# SCH_STM32CRONOS_SQUEM.net
KiCad netlist of a schematic drawn in EasyEDA
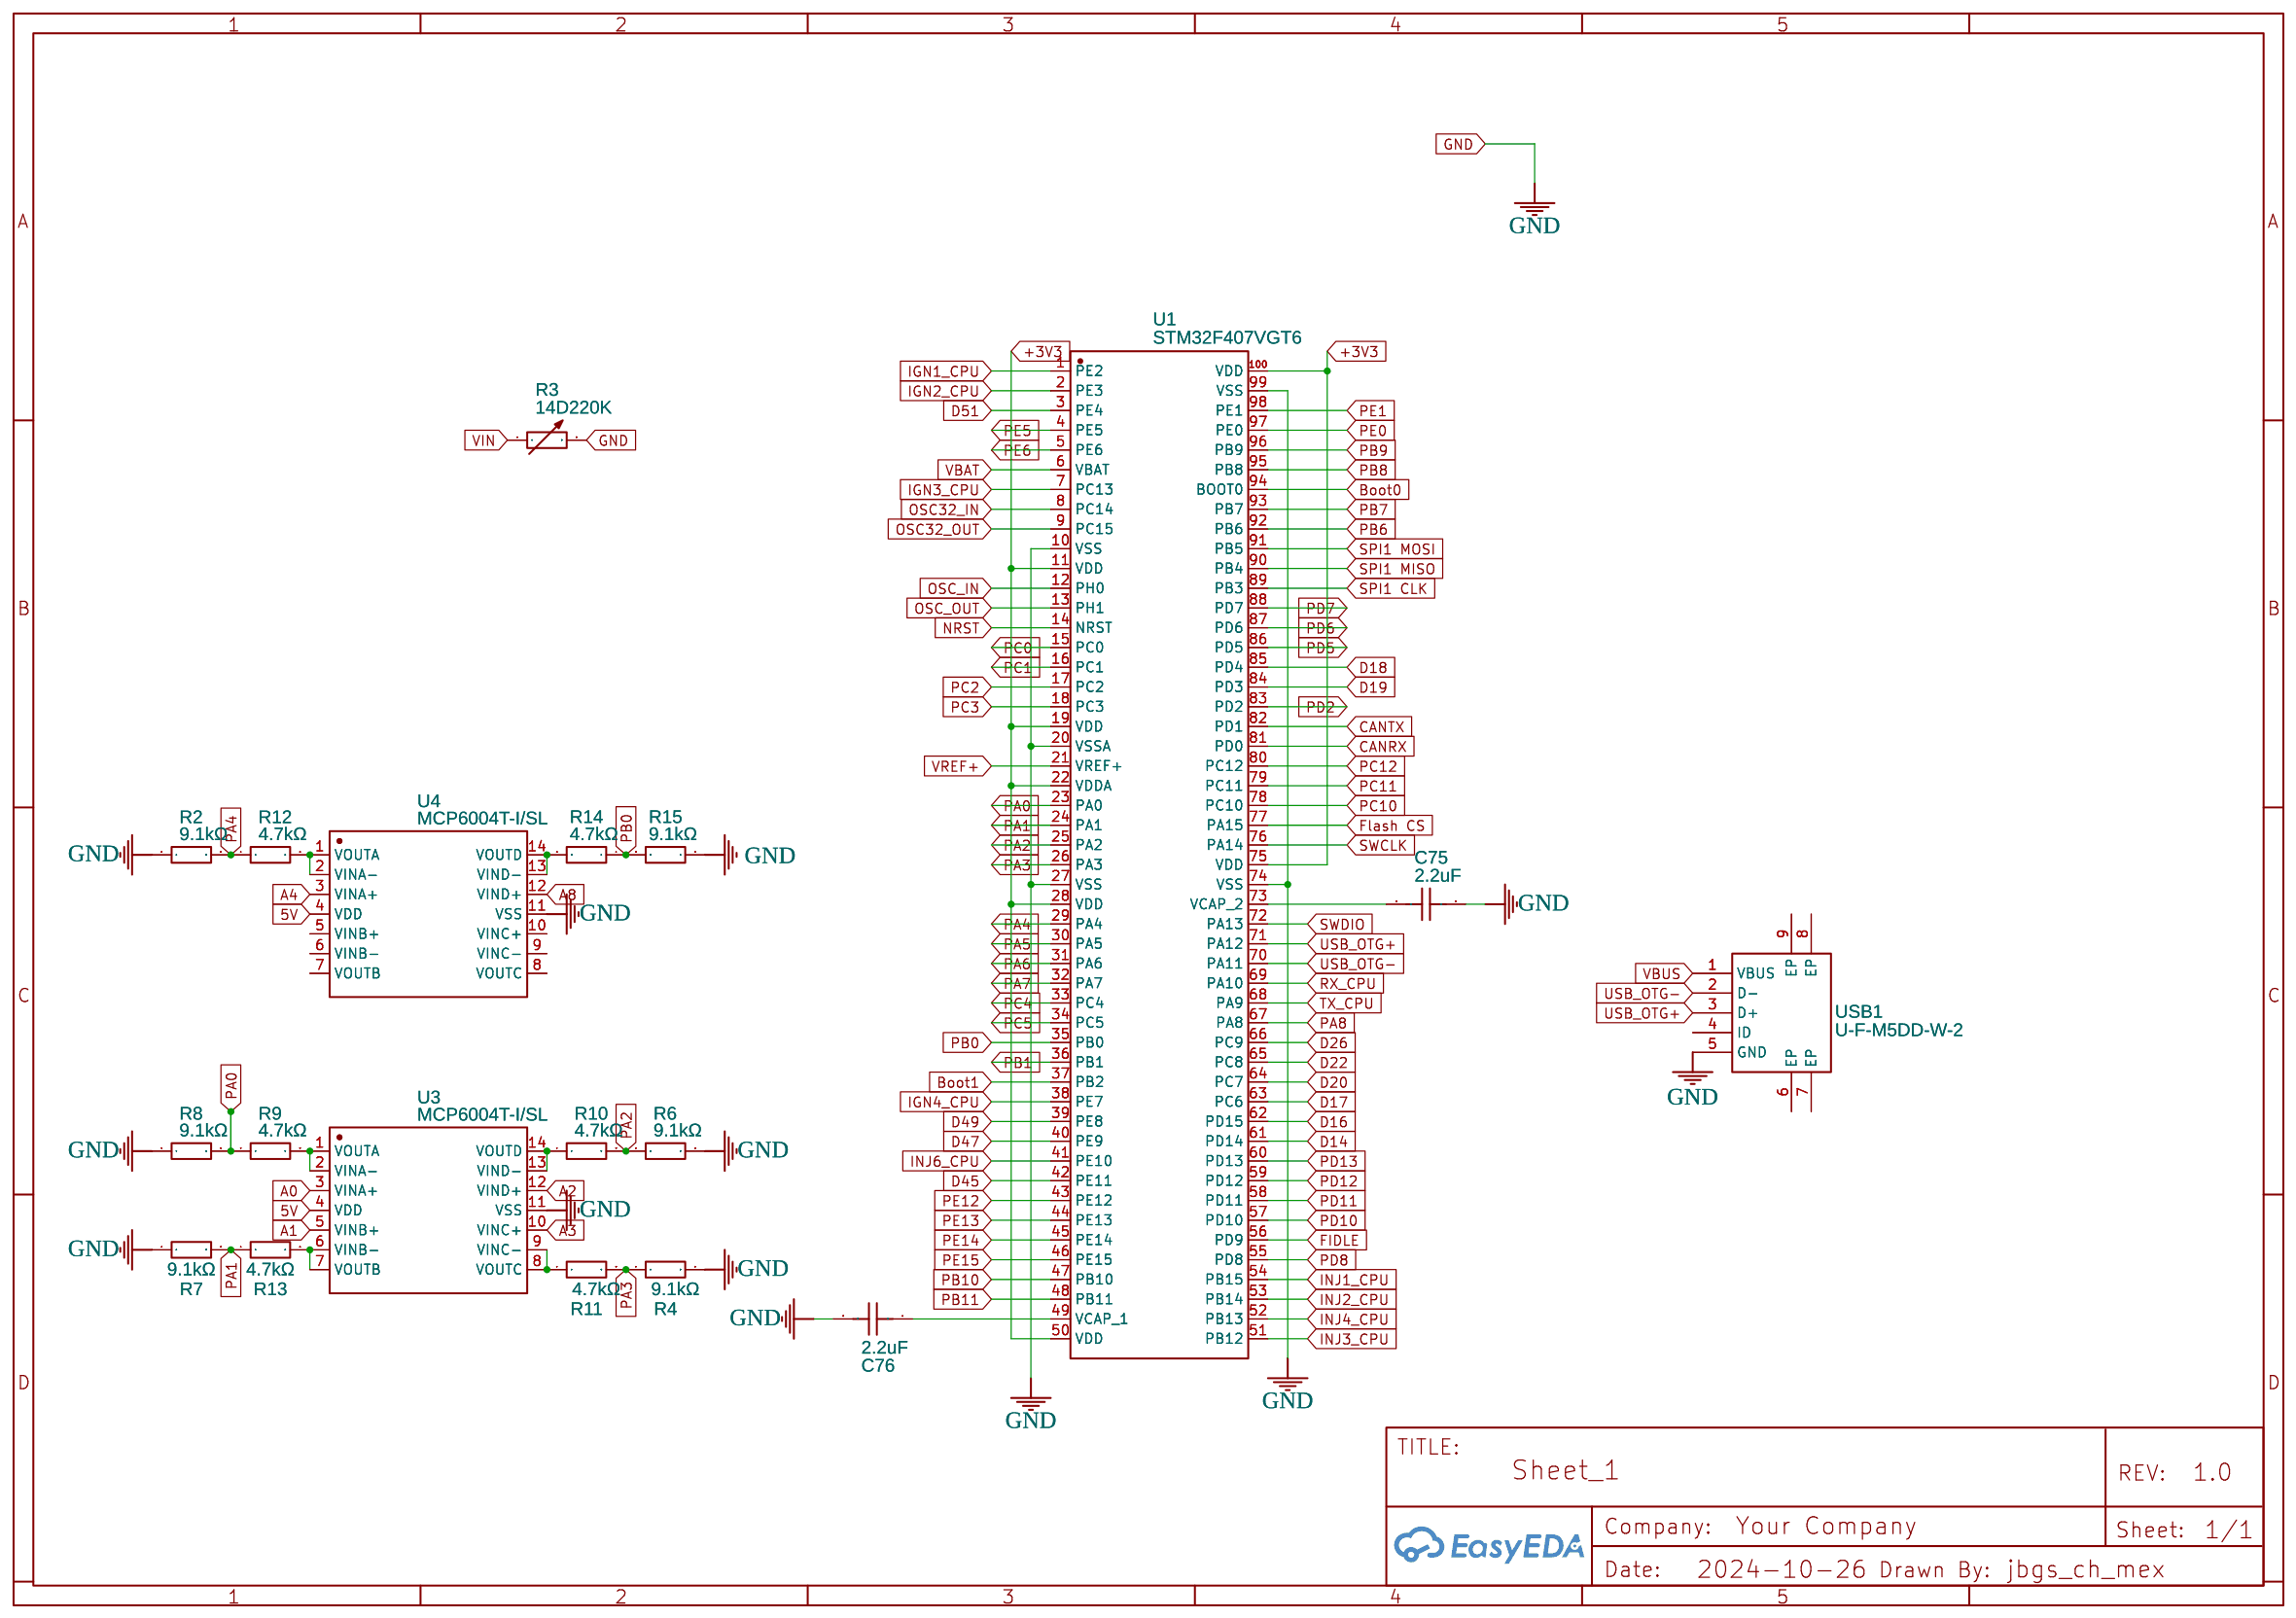
[diagram p0: Sheet_1]
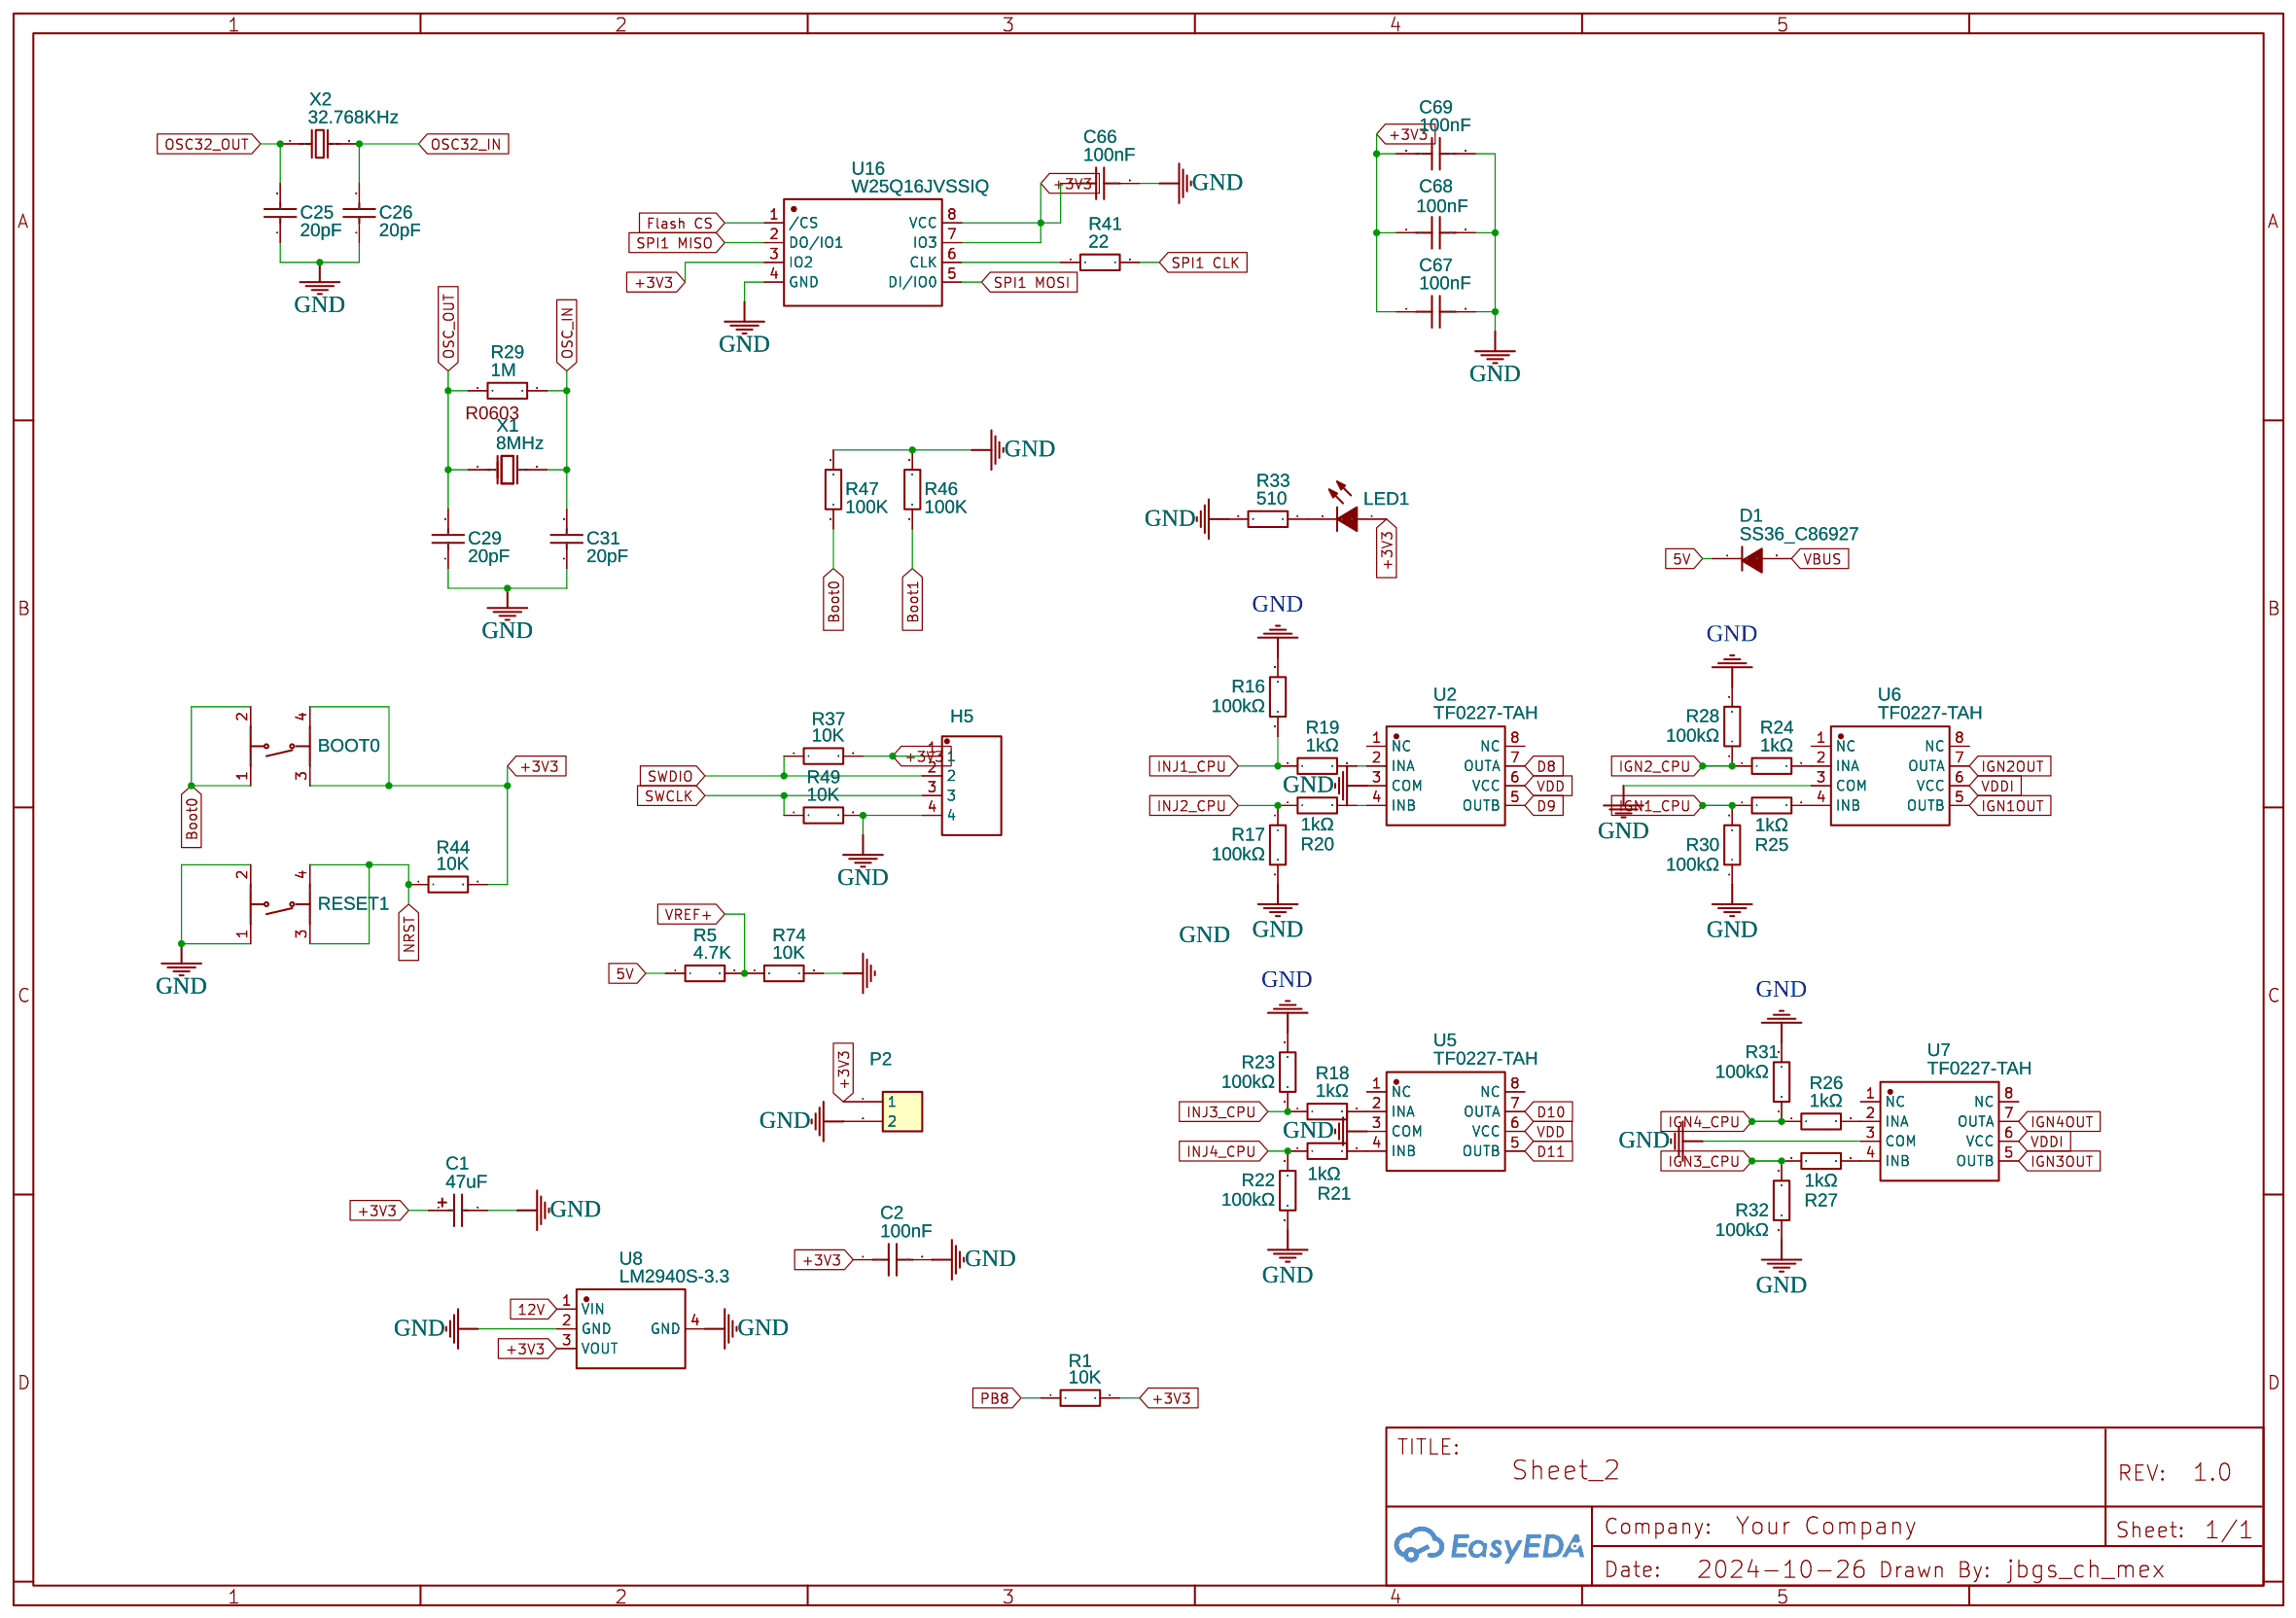
[diagram p1: Sheet_2]
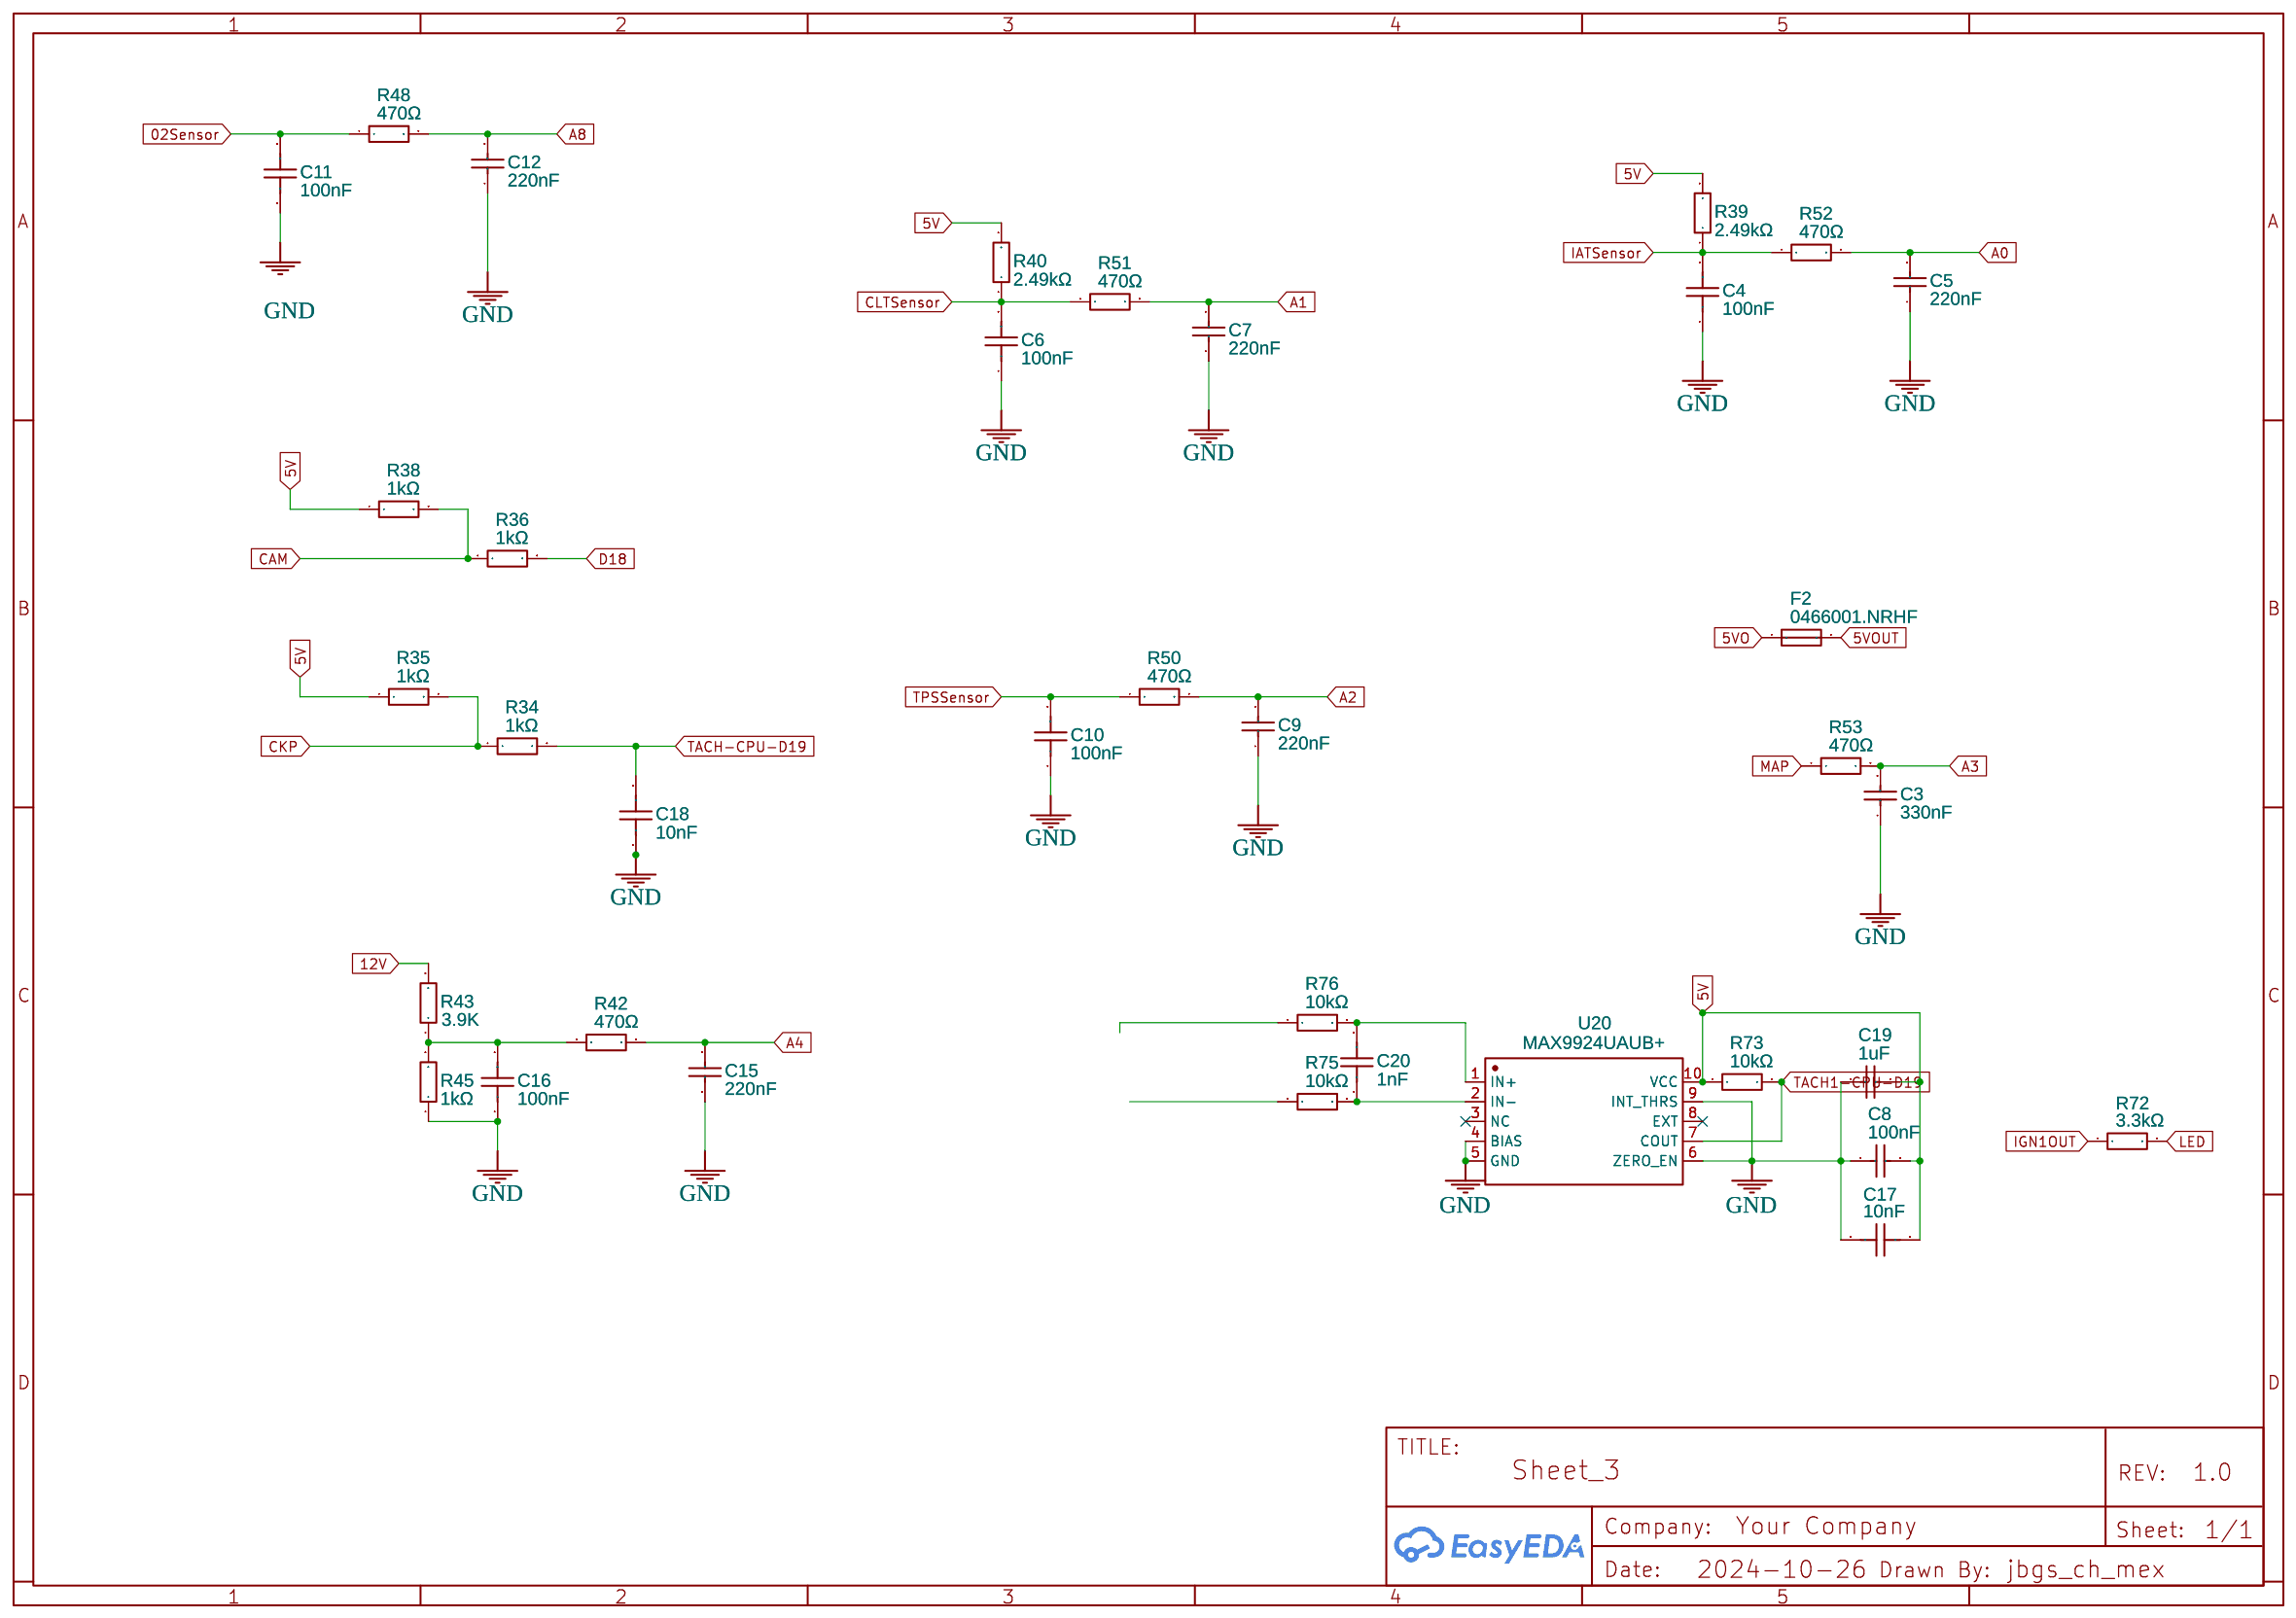
[diagram p2: Sheet_3]
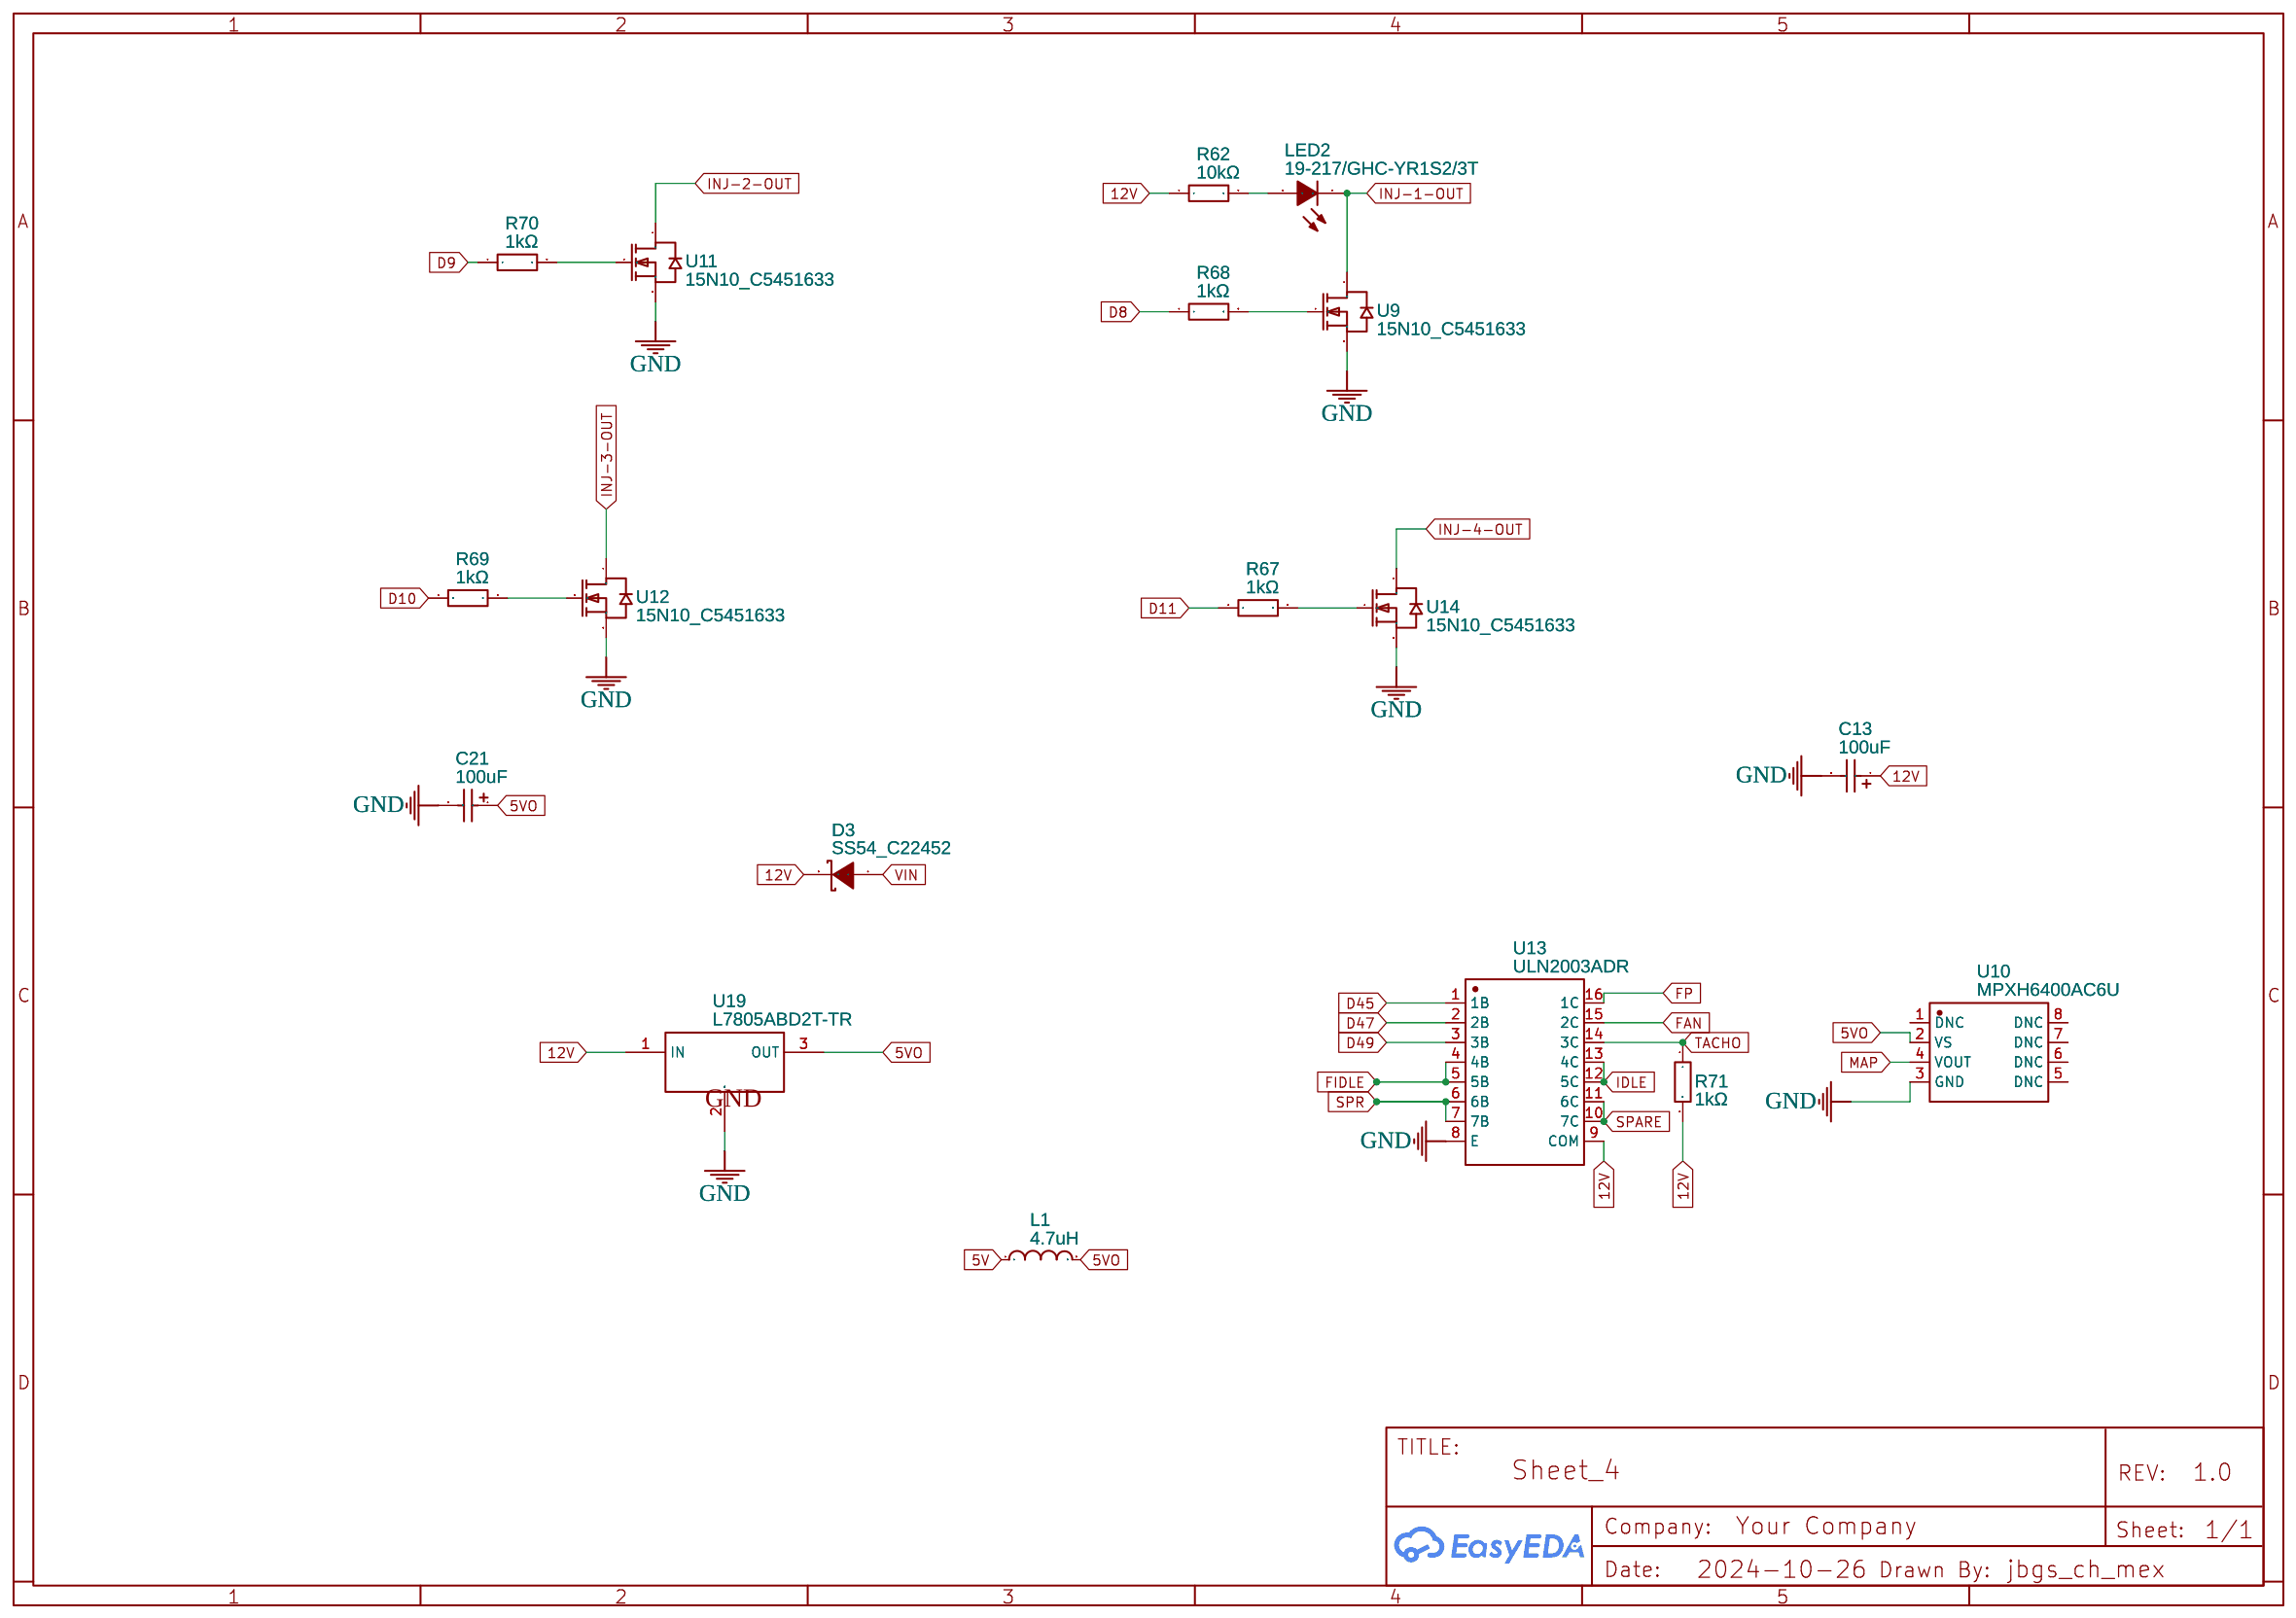
[diagram p3: Sheet_4]

(export (version "E")
  (design (tool "Eeschema 10.0.6"))
  (components
    (comp (ref "C75")
      (value "2.2uF")
      (fields (field (name "Manufacturer Part") "CL10A225KA8NNNC") (field (name "Manufacturer") "SAMSUNG"))
      (libsource (lib "") (part "CL10A225KA8NNNC_1"))
    )
    (comp (ref "C76")
      (value "2.2uF")
      (fields (field (name "Manufacturer Part") "CL10A225KA8NNNC") (field (name "Manufacturer") "SAMSUNG"))
      (libsource (lib "") (part "CL10A225KA8NNNC"))
    )
    (comp (ref "R2")
      (value "9.1kΩ")
      (fields
        (field (name "Manufacturer Part") "0603WAF9101T5E")
        (field (name "Manufacturer") "UNI-ROYAL(厚声)")
      )
      (libsource (lib "") (part "0603WAF9101T5E"))
    )
    (comp (ref "R3")
      (value "14D220K")
      (fields (field (name "Manufacturer") "HEL(鸿志)"))
      (libsource (lib "") (part "14D220K"))
    )
    (comp (ref "R4")
      (value "9.1kΩ")
      (fields
        (field (name "Manufacturer Part") "0603WAF9101T5E")
        (field (name "Manufacturer") "UNI-ROYAL(厚声)")
      )
      (libsource (lib "") (part "0603WAF9101T5E"))
    )
    (comp (ref "R6")
      (value "9.1kΩ")
      (fields
        (field (name "Manufacturer Part") "0603WAF9101T5E")
        (field (name "Manufacturer") "UNI-ROYAL(厚声)")
      )
      (libsource (lib "") (part "0603WAF9101T5E"))
    )
    (comp (ref "R7")
      (value "9.1kΩ")
      (fields
        (field (name "Manufacturer Part") "0603WAF9101T5E")
        (field (name "Manufacturer") "UNI-ROYAL(厚声)")
      )
      (libsource (lib "") (part "0603WAF9101T5E"))
    )
    (comp (ref "R8")
      (value "9.1kΩ")
      (fields
        (field (name "Manufacturer Part") "0603WAF9101T5E")
        (field (name "Manufacturer") "UNI-ROYAL(厚声)")
      )
      (libsource (lib "") (part "0603WAF9101T5E"))
    )
    (comp (ref "R9")
      (value "4.7kΩ")
      (fields (field (name "Manufacturer Part") "RMC06034K7FN") (field (name "Manufacturer") "Tyohm(幸亚电阻)"))
      (libsource (lib "") (part "RMC06034.7K1%N"))
    )
    (comp (ref "R10")
      (value "4.7kΩ")
      (fields (field (name "Manufacturer Part") "RMC06034K7FN") (field (name "Manufacturer") "Tyohm(幸亚电阻)"))
      (libsource (lib "") (part "RMC06034.7K1%N"))
    )
    (comp (ref "R11")
      (value "4.7kΩ")
      (fields (field (name "Manufacturer Part") "RMC06034K7FN") (field (name "Manufacturer") "Tyohm(幸亚电阻)"))
      (libsource (lib "") (part "RMC06034.7K1%N"))
    )
    (comp (ref "R12")
      (value "4.7kΩ")
      (fields (field (name "Manufacturer Part") "RMC06034K7FN") (field (name "Manufacturer") "Tyohm(幸亚电阻)"))
      (libsource (lib "") (part "RMC06034.7K1%N"))
    )
    (comp (ref "R13")
      (value "4.7kΩ")
      (fields (field (name "Manufacturer Part") "RMC06034K7FN") (field (name "Manufacturer") "Tyohm(幸亚电阻)"))
      (libsource (lib "") (part "RMC06034.7K1%N"))
    )
    (comp (ref "R14")
      (value "4.7kΩ")
      (fields (field (name "Manufacturer Part") "RMC06034K7FN") (field (name "Manufacturer") "Tyohm(幸亚电阻)"))
      (libsource (lib "") (part "RMC06034.7K1%N_1"))
    )
    (comp (ref "R15")
      (value "9.1kΩ")
      (fields
        (field (name "Manufacturer Part") "0603WAF9101T5E")
        (field (name "Manufacturer") "UNI-ROYAL(厚声)")
      )
      (libsource (lib "") (part "0603WAF9101T5E_1"))
    )
    (comp (ref "U1")
      (value "STM32F407VGT6")
      (fields (field (name "Manufacturer") "ST(意法半导体)"))
      (libsource (lib "") (part "STM32F407VGT6"))
    )
    (comp (ref "U3")
      (value "MCP6004T-I/SL")
      (fields (field (name "Manufacturer") "MICROCHIP(美国微芯)"))
      (libsource (lib "") (part "MCP6004T-I/SL"))
    )
    (comp (ref "U4")
      (value "MCP6004T-I/SL")
      (fields (field (name "Manufacturer") "MICROCHIP(美国微芯)"))
      (libsource (lib "") (part "MCP6004T-I/SL"))
    )
    (comp (ref "USB1")
      (value "U-F-M5DD-W-2")
      (fields (field (name "Manufacturer") "韩国韩荣"))
      (libsource (lib "") (part "U-F-M5DD-W-2"))
    )
    (comp (ref "BOOT0")
      (value "TS-1089S-02526")
      (fields (field (name "Manufacturer") "XUNPU"))
      (libsource (lib "") (part "TS-1089S-02526_1"))
    )
    (comp (ref "C1")
      (value "47uF")
      (fields (field (name "Manufacturer Part") "TAJA476K006RNJ") (field (name "Manufacturer") "Kyocera AVX"))
      (libsource (lib "") (part "TAJA476K006RNJ"))
    )
    (comp (ref "C2")
      (value "100nF")
      (fields
        (field (name "Manufacturer Part") "CC0603KRX7R9BB104")
        (field (name "Manufacturer") "YAGEO(国巨)")
      )
      (libsource (lib "") (part "CC0603KRX7R9BB104"))
    )
    (comp (ref "C25") (value "20pF") (libsource (lib "") (part "CL05C200JB5NNNC")))
    (comp (ref "C26") (value "20pF") (libsource (lib "") (part "CL05C200JB5NNNC")))
    (comp (ref "C29") (value "20pF") (libsource (lib "") (part "CL05C200JB5NNNC")))
    (comp (ref "C31") (value "20pF") (libsource (lib "") (part "CL05C200JB5NNNC")))
    (comp (ref "C66")
      (value "100nF")
      (fields
        (field (name "Manufacturer Part") "C0603X104K050T")
        (field (name "Manufacturer") "Holy Stone Enterprise")
      )
      (libsource (lib "") (part "C0603X104K050T"))
    )
    (comp (ref "C67")
      (value "100nF")
      (fields
        (field (name "Manufacturer Part") "C0603X104K050T")
        (field (name "Manufacturer") "Holy Stone Enterprise")
      )
      (libsource (lib "") (part "C0603X104K050T"))
    )
    (comp (ref "C68")
      (value "100nF")
      (fields
        (field (name "Manufacturer Part") "C0603X104K050T")
        (field (name "Manufacturer") "Holy Stone Enterprise")
      )
      (libsource (lib "") (part "C0603X104K050T"))
    )
    (comp (ref "C69")
      (value "100nF")
      (fields
        (field (name "Manufacturer Part") "C0603X104K050T")
        (field (name "Manufacturer") "Holy Stone Enterprise")
      )
      (libsource (lib "") (part "C0603X104K050T"))
    )
    (comp (ref "D1")
      (value "SS36_C86927")
      (fields (field (name "Manufacturer Part") "SS36") (field (name "Manufacturer") "DIYI(迪一/芯诺)"))
      (libsource (lib "") (part "SS36_C86927"))
    )
    (comp (ref "H5")
      (value "Header-Male-2.54_1x4_C124378")
      (fields
        (field (name "Manufacturer Part") "210S-1*4P L=11.6MMGold-plated black")
        (field (name "Manufacturer") "Ckmtw")
      )
      (libsource (lib "") (part "Header-Male-2.54_1x4_C124378"))
    )
    (comp (ref "LED1")
      (value "19-217/BHC-ZL1M2RY/3T")
      (fields (field (name "Manufacturer") "EVERLIGHT"))
      (libsource (lib "") (part "19-217/BHC-ZL1M2RY/3T"))
    )
    (comp (ref "P2")
      (value "Female header1*2P copy")
      (fields (field (name "Manufacturer Part") "Female header1*2P") (field (name "Manufacturer") "BOOMELE"))
      (libsource (lib "") (part "Female header1*2P copy"))
    )
    (comp (ref "R1")
      (value "10K")
      (fields (field (name "Manufacturer Part") "RC0402FR-0710KL") (field (name "Manufacturer") "YAGEO"))
      (libsource (lib "") (part "RC0402FR-0710KL"))
    )
    (comp (ref "R5")
      (value "4.7K")
      (fields (field (name "Manufacturer Part") "0603WAF4701T5E") (field (name "Manufacturer") "UniOhm"))
      (libsource (lib "") (part "0603WAF4701T5E"))
    )
    (comp (ref "R16")
      (value "100kΩ")
      (fields
        (field (name "Manufacturer Part") "0603WAF1003T5E")
        (field (name "Manufacturer") "UNI-ROYAL(厚声)")
      )
      (libsource (lib "") (part "0603WAF1003T5E"))
    )
    (comp (ref "R17")
      (value "100kΩ")
      (fields
        (field (name "Manufacturer Part") "0603WAF1003T5E")
        (field (name "Manufacturer") "UNI-ROYAL(厚声)")
      )
      (libsource (lib "") (part "0603WAF1003T5E_1"))
    )
    (comp (ref "R18")
      (value "1kΩ")
      (fields
        (field (name "Manufacturer Part") "0603WAF1001T5E")
        (field (name "Manufacturer") "UNI-ROYAL(厚声)")
      )
      (libsource (lib "") (part "0603WAF1001T5E"))
    )
    (comp (ref "R19")
      (value "1kΩ")
      (fields
        (field (name "Manufacturer Part") "0603WAF1001T5E")
        (field (name "Manufacturer") "UNI-ROYAL(厚声)")
      )
      (libsource (lib "") (part "0603WAF1001T5E"))
    )
    (comp (ref "R20")
      (value "1kΩ")
      (fields
        (field (name "Manufacturer Part") "0603WAF1001T5E")
        (field (name "Manufacturer") "UNI-ROYAL(厚声)")
      )
      (libsource (lib "") (part "0603WAF1001T5E"))
    )
    (comp (ref "R21")
      (value "1kΩ")
      (fields
        (field (name "Manufacturer Part") "0603WAF1001T5E")
        (field (name "Manufacturer") "UNI-ROYAL(厚声)")
      )
      (libsource (lib "") (part "0603WAF1001T5E"))
    )
    (comp (ref "R22")
      (value "100kΩ")
      (fields
        (field (name "Manufacturer Part") "0603WAF1003T5E")
        (field (name "Manufacturer") "UNI-ROYAL(厚声)")
      )
      (libsource (lib "") (part "0603WAF1003T5E_1"))
    )
    (comp (ref "R23")
      (value "100kΩ")
      (fields
        (field (name "Manufacturer Part") "0603WAF1003T5E")
        (field (name "Manufacturer") "UNI-ROYAL(厚声)")
      )
      (libsource (lib "") (part "0603WAF1003T5E"))
    )
    (comp (ref "R24")
      (value "1kΩ")
      (fields
        (field (name "Manufacturer Part") "0603WAF1001T5E")
        (field (name "Manufacturer") "UNI-ROYAL(厚声)")
      )
      (libsource (lib "") (part "0603WAF1001T5E"))
    )
    (comp (ref "R25")
      (value "1kΩ")
      (fields
        (field (name "Manufacturer Part") "0603WAF1001T5E")
        (field (name "Manufacturer") "UNI-ROYAL(厚声)")
      )
      (libsource (lib "") (part "0603WAF1001T5E"))
    )
    (comp (ref "R26")
      (value "1kΩ")
      (fields
        (field (name "Manufacturer Part") "0603WAF1001T5E")
        (field (name "Manufacturer") "UNI-ROYAL(厚声)")
      )
      (libsource (lib "") (part "0603WAF1001T5E"))
    )
    (comp (ref "R27")
      (value "1kΩ")
      (fields
        (field (name "Manufacturer Part") "0603WAF1001T5E")
        (field (name "Manufacturer") "UNI-ROYAL(厚声)")
      )
      (libsource (lib "") (part "0603WAF1001T5E"))
    )
    (comp (ref "R28")
      (value "100kΩ")
      (fields
        (field (name "Manufacturer Part") "0603WAF1003T5E")
        (field (name "Manufacturer") "UNI-ROYAL(厚声)")
      )
      (libsource (lib "") (part "0603WAF1003T5E"))
    )
    (comp (ref "R29")
      (value "1M")
      (fields (field (name "Manufacturer Part") "0402WGF1004TCE") (field (name "Manufacturer") "UniOhm"))
      (libsource (lib "") (part "0402WGF1004TCE"))
    )
    (comp (ref "R30")
      (value "100kΩ")
      (fields
        (field (name "Manufacturer Part") "0603WAF1003T5E")
        (field (name "Manufacturer") "UNI-ROYAL(厚声)")
      )
      (libsource (lib "") (part "0603WAF1003T5E"))
    )
    (comp (ref "R31")
      (value "100kΩ")
      (fields
        (field (name "Manufacturer Part") "0603WAF1003T5E")
        (field (name "Manufacturer") "UNI-ROYAL(厚声)")
      )
      (libsource (lib "") (part "0603WAF1003T5E"))
    )
    (comp (ref "R32")
      (value "100kΩ")
      (fields
        (field (name "Manufacturer Part") "0603WAF1003T5E")
        (field (name "Manufacturer") "UNI-ROYAL(厚声)")
      )
      (libsource (lib "") (part "0603WAF1003T5E"))
    )
    (comp (ref "R33")
      (value "510")
      (fields (field (name "Manufacturer Part") "0603WAF5100T5E") (field (name "Manufacturer") "UniOhm"))
      (libsource (lib "") (part "0603WAF5100T5E"))
    )
    (comp (ref "R37")
      (value "10K")
      (fields (field (name "Manufacturer Part") "RC0402FR-0710KL") (field (name "Manufacturer") "YAGEO"))
      (libsource (lib "") (part "RC0402FR-0710KL"))
    )
    (comp (ref "R41")
      (value "22")
      (fields (field (name "Manufacturer Part") "RC0402JR-0722RL") (field (name "Manufacturer") "YAGEO"))
      (libsource (lib "") (part "RC0402JR-0722RL"))
    )
    (comp (ref "R44") (value "10K") (libsource (lib "") (part "RC0402FR-0710KL")))
    (comp (ref "R46")
      (value "100K")
      (fields (field (name "Manufacturer Part") "RC0603JR-07100KL") (field (name "Manufacturer") "YAGEO"))
      (libsource (lib "") (part "RC0603JR-07100KL"))
    )
    (comp (ref "R47")
      (value "100K")
      (fields (field (name "Manufacturer Part") "RC0603JR-07100KL") (field (name "Manufacturer") "YAGEO"))
      (libsource (lib "") (part "RC0603JR-07100KL"))
    )
    (comp (ref "R49")
      (value "10K")
      (fields (field (name "Manufacturer Part") "RC0402FR-0710KL") (field (name "Manufacturer") "YAGEO"))
      (libsource (lib "") (part "RC0402FR-0710KL"))
    )
    (comp (ref "R74")
      (value "10K")
      (fields (field (name "Manufacturer Part") "0603WAF1002T5E") (field (name "Manufacturer") "UniOhm"))
      (libsource (lib "") (part "0603WAF1002T5E"))
    )
    (comp (ref "RESET1")
      (value "TS-1089S-02526")
      (fields (field (name "Manufacturer") "XUNPU"))
      (libsource (lib "") (part "TS-1089S-02526"))
    )
    (comp (ref "U2")
      (value "TF0227-TAH")
      (fields (field (name "Manufacturer") "TFSS(德律风根)"))
      (libsource (lib "") (part "TF0227-TAH"))
    )
    (comp (ref "U5")
      (value "TF0227-TAH")
      (fields (field (name "Manufacturer") "TFSS(德律风根)"))
      (libsource (lib "") (part "TF0227-TAH"))
    )
    (comp (ref "U6")
      (value "TF0227-TAH")
      (fields (field (name "Manufacturer") "TFSS(德律风根)"))
      (libsource (lib "") (part "TF0227-TAH"))
    )
    (comp (ref "U7")
      (value "TF0227-TAH")
      (fields (field (name "Manufacturer") "TFSS(德律风根)"))
      (libsource (lib "") (part "TF0227-TAH"))
    )
    (comp (ref "U8")
      (value "LM2940S-3.3")
      (fields (field (name "Manufacturer") "HTC"))
      (libsource (lib "") (part "LM2940S-3.3"))
    )
    (comp (ref "U16") (value "W25Q16JVSSIQ") (libsource (lib "") (part "W25Q16JVSSIQ")))
    (comp (ref "X1")
      (value "8MHz")
      (fields (field (name "Manufacturer Part") "X50328MSB2GI") (field (name "Manufacturer") "YXC"))
      (libsource (lib "") (part "X50328MSB2GI"))
    )
    (comp (ref "X2")
      (value "32.768KHz")
      (fields (field (name "Manufacturer Part") "Q13FC1350000400") (field (name "Manufacturer") "EPSON"))
      (libsource (lib "") (part "Q13FC1350000400"))
    )
    (comp (ref "C3")
      (value "330nF")
      (fields (field (name "Manufacturer Part") "0603B334K250NT") (field (name "Manufacturer") "FH(风华)"))
      (libsource (lib "") (part "0603B334K250NT"))
    )
    (comp (ref "C4")
      (value "100nF")
      (fields
        (field (name "Manufacturer Part") "CC0603KRX7R9BB104")
        (field (name "Manufacturer") "YAGEO(国巨)")
      )
      (libsource (lib "") (part "CC0603KRX7R9BB104"))
    )
    (comp (ref "C5")
      (value "220nF")
      (fields
        (field (name "Manufacturer Part") "CL10B224KA8NNNC")
        (field (name "Manufacturer") "SAMSUNG(三星)")
      )
      (libsource (lib "") (part "CL10B224KA8NNNC"))
    )
    (comp (ref "C6")
      (value "100nF")
      (fields
        (field (name "Manufacturer Part") "CC0603KRX7R9BB104")
        (field (name "Manufacturer") "YAGEO(国巨)")
      )
      (libsource (lib "") (part "CC0603KRX7R9BB104"))
    )
    (comp (ref "C7")
      (value "220nF")
      (fields
        (field (name "Manufacturer Part") "CL10B224KA8NNNC")
        (field (name "Manufacturer") "SAMSUNG(三星)")
      )
      (libsource (lib "") (part "CL10B224KA8NNNC"))
    )
    (comp (ref "C8")
      (value "100nF")
      (fields
        (field (name "Manufacturer Part") "CL21B104KCFNNNE")
        (field (name "Manufacturer") "SAMSUNG(三星)")
      )
      (libsource (lib "") (part "CL21B104KCFNNNE"))
    )
    (comp (ref "C9")
      (value "220nF")
      (fields
        (field (name "Manufacturer Part") "CL10B224KA8NNNC")
        (field (name "Manufacturer") "SAMSUNG(三星)")
      )
      (libsource (lib "") (part "CL10B224KA8NNNC"))
    )
    (comp (ref "C10")
      (value "100nF")
      (fields
        (field (name "Manufacturer Part") "CC0603KRX7R9BB104")
        (field (name "Manufacturer") "YAGEO(国巨)")
      )
      (libsource (lib "") (part "CC0603KRX7R9BB104"))
    )
    (comp (ref "C11")
      (value "100nF")
      (fields
        (field (name "Manufacturer Part") "CC0603KRX7R9BB104")
        (field (name "Manufacturer") "YAGEO(国巨)")
      )
      (libsource (lib "") (part "CC0603KRX7R9BB104"))
    )
    (comp (ref "C12")
      (value "220nF")
      (fields
        (field (name "Manufacturer Part") "CL10B224KA8NNNC")
        (field (name "Manufacturer") "SAMSUNG(三星)")
      )
      (libsource (lib "") (part "CL10B224KA8NNNC"))
    )
    (comp (ref "C15")
      (value "220nF")
      (fields
        (field (name "Manufacturer Part") "CL10B224KA8NNNC")
        (field (name "Manufacturer") "SAMSUNG(三星)")
      )
      (libsource (lib "") (part "CL10B224KA8NNNC"))
    )
    (comp (ref "C16")
      (value "100nF")
      (fields
        (field (name "Manufacturer Part") "CC0603KRX7R9BB104")
        (field (name "Manufacturer") "YAGEO(国巨)")
      )
      (libsource (lib "") (part "CC0603KRX7R9BB104"))
    )
    (comp (ref "C17")
      (value "10nF")
      (fields
        (field (name "Manufacturer Part") "TCC0805X7R103K500DT")
        (field (name "Manufacturer") "CCTC(三环)")
      )
      (libsource (lib "") (part "TCC0805X7R103K500DT"))
    )
    (comp (ref "C18")
      (value "10nF")
      (fields (field (name "Manufacturer Part") "C0805C103K1RAC7800") (field (name "Manufacturer") "KEMET"))
      (libsource (lib "") (part "C0805C103K1RAC7800"))
    )
    (comp (ref "C19")
      (value "1uF")
      (fields
        (field (name "Manufacturer Part") "CC0805KKX7R9BB105")
        (field (name "Manufacturer") "YAGEO(国巨)")
      )
      (libsource (lib "") (part "CC0805KKX7R9BB105"))
    )
    (comp (ref "C20")
      (value "1nF")
      (fields
        (field (name "Manufacturer Part") "CC0805KRX7RZBB102")
        (field (name "Manufacturer") "YAGEO(国巨)")
      )
      (libsource (lib "") (part "CC0805KRX7RZBB102"))
    )
    (comp (ref "F2")
      (value "0466001.NRHF")
      (fields (field (name "Manufacturer") "Littelfuse(美国力特)"))
      (libsource (lib "") (part "0466001.NRHF"))
    )
    (comp (ref "R34")
      (value "1kΩ")
      (fields
        (field (name "Manufacturer Part") "0805W8F1001T5E")
        (field (name "Manufacturer") "UNI-ROYAL(厚声)")
      )
      (libsource (lib "") (part "0805W8F1001T5E"))
    )
    (comp (ref "R35")
      (value "1kΩ")
      (fields
        (field (name "Manufacturer Part") "0805W8F1001T5E")
        (field (name "Manufacturer") "UNI-ROYAL(厚声)")
      )
      (libsource (lib "") (part "0805W8F1001T5E"))
    )
    (comp (ref "R36")
      (value "1kΩ")
      (fields
        (field (name "Manufacturer Part") "0603WAF1001T5E")
        (field (name "Manufacturer") "UNI-ROYAL(厚声)")
      )
      (libsource (lib "") (part "0603WAF1001T5E"))
    )
    (comp (ref "R38")
      (value "1kΩ")
      (fields
        (field (name "Manufacturer Part") "0603WAF1001T5E")
        (field (name "Manufacturer") "UNI-ROYAL(厚声)")
      )
      (libsource (lib "") (part "0603WAF1001T5E"))
    )
    (comp (ref "R39")
      (value "2.49kΩ")
      (fields
        (field (name "Manufacturer Part") "0805W8F2491T5E")
        (field (name "Manufacturer") "UNI-ROYAL(厚声)")
      )
      (libsource (lib "") (part "0805W8F2491T5E"))
    )
    (comp (ref "R40")
      (value "2.49kΩ")
      (fields
        (field (name "Manufacturer Part") "0805W8F2491T5E")
        (field (name "Manufacturer") "UNI-ROYAL(厚声)")
      )
      (libsource (lib "") (part "0805W8F2491T5E"))
    )
    (comp (ref "R42")
      (value "470Ω")
      (fields
        (field (name "Manufacturer Part") "0603WAF4700T5E")
        (field (name "Manufacturer") "UNI-ROYAL(厚声)")
      )
      (libsource (lib "") (part "0603WAF4700T5E"))
    )
    (comp (ref "R43")
      (value "3.9K")
      (fields (field (name "Manufacturer Part") "0603WAF3901T5E") (field (name "Manufacturer") "UniOhm"))
      (libsource (lib "") (part "0603WAF3901T5E"))
    )
    (comp (ref "R45")
      (value "1kΩ")
      (fields
        (field (name "Manufacturer Part") "0603WAF1001T5E")
        (field (name "Manufacturer") "UNI-ROYAL(厚声)")
      )
      (libsource (lib "") (part "0603WAF1001T5E_1"))
    )
    (comp (ref "R48")
      (value "470Ω")
      (fields
        (field (name "Manufacturer Part") "0603WAF4700T5E")
        (field (name "Manufacturer") "UNI-ROYAL(厚声)")
      )
      (libsource (lib "") (part "0603WAF4700T5E"))
    )
    (comp (ref "R50")
      (value "470Ω")
      (fields
        (field (name "Manufacturer Part") "0603WAF4700T5E")
        (field (name "Manufacturer") "UNI-ROYAL(厚声)")
      )
      (libsource (lib "") (part "0603WAF4700T5E"))
    )
    (comp (ref "R51")
      (value "470Ω")
      (fields
        (field (name "Manufacturer Part") "0603WAF4700T5E")
        (field (name "Manufacturer") "UNI-ROYAL(厚声)")
      )
      (libsource (lib "") (part "0603WAF4700T5E"))
    )
    (comp (ref "R52")
      (value "470Ω")
      (fields
        (field (name "Manufacturer Part") "0603WAF4700T5E")
        (field (name "Manufacturer") "UNI-ROYAL(厚声)")
      )
      (libsource (lib "") (part "0603WAF4700T5E"))
    )
    (comp (ref "R53")
      (value "470Ω")
      (fields
        (field (name "Manufacturer Part") "0603WAF4700T5E")
        (field (name "Manufacturer") "UNI-ROYAL(厚声)")
      )
      (libsource (lib "") (part "0603WAF4700T5E"))
    )
    (comp (ref "R72")
      (value "3.3kΩ")
      (fields
        (field (name "Manufacturer Part") "0805W8F3301T5E")
        (field (name "Manufacturer") "UNI-ROYAL(厚声)")
      )
      (libsource (lib "") (part "0805W8F3301T5E"))
    )
    (comp (ref "R73")
      (value "10kΩ")
      (fields
        (field (name "Manufacturer Part") "0805W8F1002T5E")
        (field (name "Manufacturer") "UNI-ROYAL(厚声)")
      )
      (libsource (lib "") (part "0805W8F1002T5E"))
    )
    (comp (ref "R75")
      (value "10kΩ")
      (fields
        (field (name "Manufacturer Part") "0805W8F1002T5E")
        (field (name "Manufacturer") "UNI-ROYAL(厚声)")
      )
      (libsource (lib "") (part "0805W8F1002T5E"))
    )
    (comp (ref "R76")
      (value "10kΩ")
      (fields
        (field (name "Manufacturer Part") "0805W8F1002T5E")
        (field (name "Manufacturer") "UNI-ROYAL(厚声)")
      )
      (libsource (lib "") (part "0805W8F1002T5E"))
    )
    (comp (ref "U20")
      (value "MAX9924UAUB+")
      (fields (field (name "Manufacturer") "ADI(亚德诺)/MAXIM(美信)"))
      (libsource (lib "") (part "MAX9924UAUB+"))
    )
    (comp (ref "C13")
      (value "100uF")
      (fields (field (name "Manufacturer Part") "TAJD107M020RNJ") (field (name "Manufacturer") "Kyocera AVX"))
      (libsource (lib "") (part "TAJD107M020RNJ"))
    )
    (comp (ref "C21")
      (value "100uF")
      (fields (field (name "Manufacturer Part") "TAJB107K006RNJ") (field (name "Manufacturer") "Kyocera AVX"))
      (libsource (lib "") (part "TAJB107K006RNJ"))
    )
    (comp (ref "D3")
      (value "SS54_C22452")
      (fields (field (name "Manufacturer Part") "SS54") (field (name "Manufacturer") "MDD(辰达半导体)"))
      (libsource (lib "") (part "SS54_C22452"))
    )
    (comp (ref "L1")
      (value "4.7uH")
      (fields (field (name "Manufacturer Part") "YSPI0530-4R7M") (field (name "Manufacturer") "YJYCOIN(益嘉源)"))
      (libsource (lib "") (part "YSPI0530-4R7M"))
    )
    (comp (ref "LED2")
      (value "19-217/GHC-YR1S2/3T")
      (fields (field (name "Manufacturer") "EVERLIGHT(亿光)"))
      (libsource (lib "") (part "19-217/GHC-YR1S2/3T"))
    )
    (comp (ref "R62")
      (value "10kΩ")
      (fields
        (field (name "Manufacturer Part") "0805W8F1002T5E")
        (field (name "Manufacturer") "UNI-ROYAL(厚声)")
      )
      (libsource (lib "") (part "0805W8F1002T5E"))
    )
    (comp (ref "R67")
      (value "1kΩ")
      (fields
        (field (name "Manufacturer Part") "0805W8F1001T5E")
        (field (name "Manufacturer") "UNI-ROYAL(厚声)")
      )
      (libsource (lib "") (part "0805W8F1001T5E"))
    )
    (comp (ref "R68")
      (value "1kΩ")
      (fields
        (field (name "Manufacturer Part") "0805W8F1001T5E")
        (field (name "Manufacturer") "UNI-ROYAL(厚声)")
      )
      (libsource (lib "") (part "0805W8F1001T5E"))
    )
    (comp (ref "R69")
      (value "1kΩ")
      (fields
        (field (name "Manufacturer Part") "0805W8F1001T5E")
        (field (name "Manufacturer") "UNI-ROYAL(厚声)")
      )
      (libsource (lib "") (part "0805W8F1001T5E"))
    )
    (comp (ref "R70")
      (value "1kΩ")
      (fields
        (field (name "Manufacturer Part") "0805W8F1001T5E")
        (field (name "Manufacturer") "UNI-ROYAL(厚声)")
      )
      (libsource (lib "") (part "0805W8F1001T5E"))
    )
    (comp (ref "R71")
      (value "1kΩ")
      (fields
        (field (name "Manufacturer Part") "0603WAF1001T5E")
        (field (name "Manufacturer") "UNI-ROYAL(厚声)")
      )
      (libsource (lib "") (part "0603WAF1001T5E"))
    )
    (comp (ref "U9")
      (value "15N10_C5451633")
      (fields (field (name "Manufacturer Part") "15N10") (field (name "Manufacturer") "HXY MOSFET(华轩阳电子)"))
      (libsource (lib "") (part "15N10_C5451633"))
    )
    (comp (ref "U10")
      (value "MPXH6400AC6U")
      (fields (field (name "Manufacturer") "NXP(恩智浦)"))
      (libsource (lib "") (part "MPXH6400AC6U"))
    )
    (comp (ref "U11")
      (value "15N10_C5451633")
      (fields (field (name "Manufacturer Part") "15N10") (field (name "Manufacturer") "HXY MOSFET(华轩阳电子)"))
      (libsource (lib "") (part "15N10_C5451633"))
    )
    (comp (ref "U12")
      (value "15N10_C5451633")
      (fields (field (name "Manufacturer Part") "15N10") (field (name "Manufacturer") "HXY MOSFET(华轩阳电子)"))
      (libsource (lib "") (part "15N10_C5451633"))
    )
    (comp (ref "U13")
      (value "ULN2003ADR")
      (fields (field (name "Manufacturer") "TI(德州仪器)"))
      (libsource (lib "") (part "ULN2003ADR"))
    )
    (comp (ref "U14")
      (value "15N10_C5451633")
      (fields (field (name "Manufacturer Part") "15N10") (field (name "Manufacturer") "HXY MOSFET(华轩阳电子)"))
      (libsource (lib "") (part "15N10_C5451633"))
    )
    (comp (ref "U19")
      (value "L7805ABD2T-TR")
      (fields (field (name "Manufacturer") "ST(意法半导体)"))
      (libsource (lib "") (part "L7805ABD2T-TR"))
    )
  )
  (nets
    (net (code "1") (name "+3V3") (class "Default")
      (node (ref "BOOT0") (pin "3") (pinfunction "3_3") (pintype "unspecified"))
      (node (ref "BOOT0") (pin "4") (pinfunction "4_4") (pintype "unspecified"))
      (node (ref "C1") (pin "1") (pinfunction "1_1") (pintype "input"))
      (node (ref "C2") (pin "1") (pinfunction "1_1") (pintype "unspecified"))
      (node (ref "C66") (pin "1") (pinfunction "1_1") (pintype "unspecified"))
      (node (ref "C67") (pin "1") (pinfunction "1_1") (pintype "unspecified"))
      (node (ref "C68") (pin "1") (pinfunction "1_1") (pintype "unspecified"))
      (node (ref "C69") (pin "1") (pinfunction "1_1") (pintype "unspecified"))
      (node (ref "H5") (pin "1") (pinfunction "1_1") (pintype "unspecified"))
      (node (ref "LED1") (pin "1") (pinfunction "A_1") (pintype "input"))
      (node (ref "P2") (pin "1") (pinfunction "1_1") (pintype "input"))
      (node (ref "R1") (pin "2") (pinfunction "2_2") (pintype "input"))
      (node (ref "R37") (pin "2") (pinfunction "2_2") (pintype "input"))
      (node (ref "R44") (pin "2") (pinfunction "2_2") (pintype "input"))
      (node (ref "U1") (pin "100") (pinfunction "VDD_100") (pintype "unspecified"))
      (node (ref "U1") (pin "11") (pinfunction "VDD_11") (pintype "unspecified"))
      (node (ref "U1") (pin "19") (pinfunction "VDD_19") (pintype "unspecified"))
      (node (ref "U1") (pin "22") (pinfunction "VDDA_22") (pintype "unspecified"))
      (node (ref "U1") (pin "28") (pinfunction "VDD_28") (pintype "unspecified"))
      (node (ref "U1") (pin "50") (pinfunction "VDD_50") (pintype "unspecified"))
      (node (ref "U1") (pin "75") (pinfunction "VDD_75") (pintype "unspecified"))
      (node (ref "U16") (pin "3") (pinfunction "IO2_3") (pintype "unspecified"))
      (node (ref "U16") (pin "7") (pinfunction "IO3_7") (pintype "unspecified"))
      (node (ref "U16") (pin "8") (pinfunction "VCC_8") (pintype "unspecified"))
      (node (ref "U8") (pin "3") (pinfunction "VOUT_3") (pintype "unspecified"))
    )
    (net (code "2") (name "02Sensor") (class "Default")
      (node (ref "C11") (pin "2") (pinfunction "2_2") (pintype "unspecified"))
      (node (ref "R48") (pin "1") (pinfunction "1_1") (pintype "input"))
    )
    (net (code "3") (name "5V") (class "Default")
      (node (ref "C17") (pin "1") (pinfunction "1_1") (pintype "unspecified"))
      (node (ref "C19") (pin "2") (pinfunction "2_2") (pintype "input"))
      (node (ref "C8") (pin "2") (pinfunction "2_2") (pintype "input"))
      (node (ref "D1") (pin "1") (pinfunction "C_1") (pintype "unspecified"))
      (node (ref "L1") (pin "1") (pinfunction "1_1") (pintype "unspecified"))
      (node (ref "R35") (pin "1") (pinfunction "1_1") (pintype "input"))
      (node (ref "R38") (pin "1") (pinfunction "1_1") (pintype "input"))
      (node (ref "R39") (pin "2") (pinfunction "2_2") (pintype "input"))
      (node (ref "R40") (pin "2") (pinfunction "2_2") (pintype "input"))
      (node (ref "R5") (pin "1") (pinfunction "1_1") (pintype "input"))
      (node (ref "R73") (pin "1") (pinfunction "1_1") (pintype "input"))
      (node (ref "U20") (pin "10") (pinfunction "VCC_10") (pintype "unspecified"))
      (node (ref "U3") (pin "4") (pinfunction "VDD_4") (pintype "unspecified"))
      (node (ref "U4") (pin "4") (pinfunction "VDD_4") (pintype "unspecified"))
    )
    (net (code "4") (name "5VO") (class "Default")
      (node (ref "C21") (pin "1") (pinfunction "1_1") (pintype "input"))
      (node (ref "F2") (pin "1") (pinfunction "1_1") (pintype "unspecified"))
      (node (ref "L1") (pin "2") (pinfunction "2_2") (pintype "unspecified"))
      (node (ref "U10") (pin "2") (pinfunction "VS_2") (pintype "unspecified"))
      (node (ref "U19") (pin "3") (pinfunction "OUT_3") (pintype "passive"))
    )
    (net (code "5") (name "5VOUT") (class "Default")
      (node (ref "F2") (pin "2") (pinfunction "2_2") (pintype "unspecified"))
    )
    (net (code "6") (name "12V") (class "Default")
      (node (ref "C13") (pin "1") (pinfunction "1_1") (pintype "input"))
      (node (ref "D3") (pin "2") (pinfunction "K_2") (pintype "unspecified"))
      (node (ref "R43") (pin "2") (pinfunction "2_2") (pintype "input"))
      (node (ref "R62") (pin "1") (pinfunction "1_1") (pintype "input"))
      (node (ref "R71") (pin "2") (pinfunction "2_2") (pintype "input"))
      (node (ref "U13") (pin "9") (pinfunction "COM_9") (pintype "unspecified"))
      (node (ref "U19") (pin "1") (pinfunction "IN_1") (pintype "passive"))
      (node (ref "U8") (pin "1") (pinfunction "VIN_1") (pintype "unspecified"))
    )
    (net (code "7") (name "A0") (class "Default")
      (node (ref "C5") (pin "2") (pinfunction "2_2") (pintype "input"))
      (node (ref "R52") (pin "2") (pinfunction "2_2") (pintype "input"))
      (node (ref "U3") (pin "3") (pinfunction "VINA+_3") (pintype "unspecified"))
    )
    (net (code "8") (name "A1") (class "Default")
      (node (ref "C7") (pin "2") (pinfunction "2_2") (pintype "input"))
      (node (ref "R51") (pin "2") (pinfunction "2_2") (pintype "input"))
      (node (ref "U3") (pin "5") (pinfunction "VINB+_5") (pintype "unspecified"))
    )
    (net (code "9") (name "A2") (class "Default")
      (node (ref "C9") (pin "2") (pinfunction "2_2") (pintype "input"))
      (node (ref "R50") (pin "2") (pinfunction "2_2") (pintype "input"))
      (node (ref "U3") (pin "12") (pinfunction "VIND+_12") (pintype "unspecified"))
    )
    (net (code "10") (name "A3") (class "Default")
      (node (ref "C3") (pin "2") (pinfunction "2_2") (pintype "input"))
      (node (ref "R53") (pin "2") (pinfunction "2_2") (pintype "input"))
      (node (ref "U3") (pin "10") (pinfunction "VINC+_10") (pintype "unspecified"))
    )
    (net (code "11") (name "A4") (class "Default")
      (node (ref "C15") (pin "2") (pinfunction "2_2") (pintype "input"))
      (node (ref "R42") (pin "2") (pinfunction "2_2") (pintype "input"))
      (node (ref "U4") (pin "3") (pinfunction "VINA+_3") (pintype "unspecified"))
    )
    (net (code "12") (name "A8") (class "Default")
      (node (ref "C12") (pin "2") (pinfunction "2_2") (pintype "input"))
      (node (ref "R48") (pin "2") (pinfunction "2_2") (pintype "input"))
      (node (ref "U4") (pin "12") (pinfunction "VIND+_12") (pintype "unspecified"))
    )
    (net (code "13") (name "Boot0") (class "Default")
      (node (ref "BOOT0") (pin "1") (pinfunction "1_1") (pintype "unspecified"))
      (node (ref "BOOT0") (pin "2") (pinfunction "2_2") (pintype "unspecified"))
      (node (ref "R47") (pin "1") (pinfunction "1_1") (pintype "unspecified"))
      (node (ref "U1") (pin "94") (pinfunction "BOOT0_94") (pintype "unspecified"))
    )
    (net (code "14") (name "Boot1") (class "Default")
      (node (ref "R46") (pin "1") (pinfunction "1_1") (pintype "unspecified"))
      (node (ref "U1") (pin "37") (pinfunction "PB2_37") (pintype "unspecified"))
    )
    (net (code "15") (name "CAM") (class "Default")
      (node (ref "R36") (pin "1") (pinfunction "1_1") (pintype "input"))
      (node (ref "R38") (pin "2") (pinfunction "2_2") (pintype "input"))
    )
    (net (code "16") (name "CANRX") (class "Default")
      (node (ref "U1") (pin "81") (pinfunction "PD0_81") (pintype "unspecified"))
    )
    (net (code "17") (name "CANTX") (class "Default")
      (node (ref "U1") (pin "82") (pinfunction "PD1_82") (pintype "unspecified"))
    )
    (net (code "18") (name "CKP") (class "Default")
      (node (ref "R34") (pin "1") (pinfunction "1_1") (pintype "input"))
      (node (ref "R35") (pin "2") (pinfunction "2_2") (pintype "input"))
    )
    (net (code "19") (name "CLTSensor") (class "Default")
      (node (ref "C6") (pin "2") (pinfunction "2_2") (pintype "unspecified"))
      (node (ref "R40") (pin "1") (pinfunction "1_1") (pintype "input"))
      (node (ref "R51") (pin "1") (pinfunction "1_1") (pintype "input"))
    )
    (net (code "20") (name "D8") (class "Default")
      (node (ref "R68") (pin "1") (pinfunction "1_1") (pintype "input"))
      (node (ref "U2") (pin "7") (pinfunction "OUTA_7") (pintype "unspecified"))
    )
    (net (code "21") (name "D9") (class "Default")
      (node (ref "R70") (pin "1") (pinfunction "1_1") (pintype "input"))
      (node (ref "U2") (pin "5") (pinfunction "OUTB_5") (pintype "unspecified"))
    )
    (net (code "22") (name "D10") (class "Default")
      (node (ref "R69") (pin "1") (pinfunction "1_1") (pintype "input"))
      (node (ref "U5") (pin "7") (pinfunction "OUTA_7") (pintype "unspecified"))
    )
    (net (code "23") (name "D11") (class "Default")
      (node (ref "R67") (pin "1") (pinfunction "1_1") (pintype "input"))
      (node (ref "U5") (pin "5") (pinfunction "OUTB_5") (pintype "unspecified"))
    )
    (net (code "24") (name "D14") (class "Default")
      (node (ref "U1") (pin "61") (pinfunction "PD14_61") (pintype "unspecified"))
    )
    (net (code "25") (name "D16") (class "Default")
      (node (ref "U1") (pin "62") (pinfunction "PD15_62") (pintype "unspecified"))
    )
    (net (code "26") (name "D17") (class "Default")
      (node (ref "U1") (pin "63") (pinfunction "PC6_63") (pintype "unspecified"))
    )
    (net (code "27") (name "D18") (class "Default")
      (node (ref "R36") (pin "2") (pinfunction "2_2") (pintype "input"))
      (node (ref "U1") (pin "85") (pinfunction "PD4_85") (pintype "unspecified"))
    )
    (net (code "28") (name "D19") (class "Default")
      (node (ref "U1") (pin "84") (pinfunction "PD3_84") (pintype "unspecified"))
    )
    (net (code "29") (name "D20") (class "Default")
      (node (ref "U1") (pin "64") (pinfunction "PC7_64") (pintype "unspecified"))
    )
    (net (code "30") (name "D22") (class "Default")
      (node (ref "U1") (pin "65") (pinfunction "PC8_65") (pintype "unspecified"))
    )
    (net (code "31") (name "D26") (class "Default")
      (node (ref "U1") (pin "66") (pinfunction "PC9_66") (pintype "unspecified"))
    )
    (net (code "32") (name "D45") (class "Default")
      (node (ref "U1") (pin "42") (pinfunction "PE11_42") (pintype "unspecified"))
      (node (ref "U13") (pin "1") (pinfunction "1B_1") (pintype "unspecified"))
    )
    (net (code "33") (name "D47") (class "Default")
      (node (ref "U1") (pin "40") (pinfunction "PE9_40") (pintype "unspecified"))
      (node (ref "U13") (pin "2") (pinfunction "2B_2") (pintype "unspecified"))
    )
    (net (code "34") (name "D49") (class "Default")
      (node (ref "U1") (pin "39") (pinfunction "PE8_39") (pintype "unspecified"))
      (node (ref "U13") (pin "3") (pinfunction "3B_3") (pintype "unspecified"))
    )
    (net (code "35") (name "D51") (class "Default")
      (node (ref "U1") (pin "3") (pinfunction "PE4_3") (pintype "unspecified"))
    )
    (net (code "36") (name "FAN") (class "Default")
      (node (ref "U13") (pin "15") (pinfunction "2C_15") (pintype "unspecified"))
    )
    (net (code "37") (name "FIDLE") (class "Default")
      (node (ref "U1") (pin "56") (pinfunction "PD9_56") (pintype "unspecified"))
      (node (ref "U13") (pin "4") (pinfunction "4B_4") (pintype "unspecified"))
      (node (ref "U13") (pin "5") (pinfunction "5B_5") (pintype "unspecified"))
    )
    (net (code "38") (name "FP") (class "Default")
      (node (ref "U13") (pin "16") (pinfunction "1C_16") (pintype "unspecified"))
    )
    (net (code "39") (name "Flash CS") (class "Default")
      (node (ref "U1") (pin "77") (pinfunction "PA15_77") (pintype "unspecified"))
      (node (ref "U16") (pin "1") (pinfunction "/CS_1") (pintype "unspecified"))
    )
    (net (code "40") (name "GND") (class "Default")
      (node (ref "C1") (pin "2") (pinfunction "2_2") (pintype "input"))
      (node (ref "C10") (pin "1") (pinfunction "1_1") (pintype "unspecified"))
      (node (ref "C11") (pin "1") (pinfunction "1_1") (pintype "unspecified"))
      (node (ref "C12") (pin "1") (pinfunction "1_1") (pintype "input"))
      (node (ref "C13") (pin "2") (pinfunction "2_2") (pintype "input"))
      (node (ref "C15") (pin "1") (pinfunction "1_1") (pintype "input"))
      (node (ref "C16") (pin "1") (pinfunction "1_1") (pintype "unspecified"))
      (node (ref "C17") (pin "2") (pinfunction "2_2") (pintype "unspecified"))
      (node (ref "C18") (pin "1") (pinfunction "1_1") (pintype "unspecified"))
      (node (ref "C19") (pin "1") (pinfunction "1_1") (pintype "input"))
      (node (ref "C2") (pin "2") (pinfunction "2_2") (pintype "unspecified"))
      (node (ref "C21") (pin "2") (pinfunction "2_2") (pintype "input"))
      (node (ref "C25") (pin "1") (pinfunction "1_1") (pintype "input"))
      (node (ref "C26") (pin "1") (pinfunction "1_1") (pintype "input"))
      (node (ref "C29") (pin "1") (pinfunction "1_1") (pintype "input"))
      (node (ref "C3") (pin "1") (pinfunction "1_1") (pintype "input"))
      (node (ref "C31") (pin "1") (pinfunction "1_1") (pintype "input"))
      (node (ref "C4") (pin "1") (pinfunction "1_1") (pintype "unspecified"))
      (node (ref "C5") (pin "1") (pinfunction "1_1") (pintype "input"))
      (node (ref "C6") (pin "1") (pinfunction "1_1") (pintype "unspecified"))
      (node (ref "C66") (pin "2") (pinfunction "2_2") (pintype "unspecified"))
      (node (ref "C67") (pin "2") (pinfunction "2_2") (pintype "unspecified"))
      (node (ref "C68") (pin "2") (pinfunction "2_2") (pintype "unspecified"))
      (node (ref "C69") (pin "2") (pinfunction "2_2") (pintype "unspecified"))
      (node (ref "C7") (pin "1") (pinfunction "1_1") (pintype "input"))
      (node (ref "C75") (pin "1") (pinfunction "1_1") (pintype "unspecified"))
      (node (ref "C76") (pin "2") (pinfunction "2_2") (pintype "unspecified"))
      (node (ref "C8") (pin "1") (pinfunction "1_1") (pintype "input"))
      (node (ref "C9") (pin "1") (pinfunction "1_1") (pintype "input"))
      (node (ref "H5") (pin "4") (pinfunction "4_4") (pintype "unspecified"))
      (node (ref "P2") (pin "2") (pinfunction "2_2") (pintype "input"))
      (node (ref "R15") (pin "1") (pinfunction "1_1") (pintype "input"))
      (node (ref "R16") (pin "2") (pinfunction "2_2") (pintype "input"))
      (node (ref "R17") (pin "2") (pinfunction "2_2") (pintype "input"))
      (node (ref "R2") (pin "1") (pinfunction "1_1") (pintype "input"))
      (node (ref "R22") (pin "2") (pinfunction "2_2") (pintype "input"))
      (node (ref "R23") (pin "2") (pinfunction "2_2") (pintype "input"))
      (node (ref "R28") (pin "2") (pinfunction "2_2") (pintype "input"))
      (node (ref "R3") (pin "2") (pinfunction "2_2") (pintype "unspecified"))
      (node (ref "R30") (pin "1") (pinfunction "1_1") (pintype "input"))
      (node (ref "R31") (pin "2") (pinfunction "2_2") (pintype "input"))
      (node (ref "R32") (pin "1") (pinfunction "1_1") (pintype "input"))
      (node (ref "R33") (pin "2") (pinfunction "2_2") (pintype "input"))
      (node (ref "R4") (pin "2") (pinfunction "2_2") (pintype "input"))
      (node (ref "R45") (pin "1") (pinfunction "1_1") (pintype "input"))
      (node (ref "R46") (pin "2") (pinfunction "2_2") (pintype "unspecified"))
      (node (ref "R47") (pin "2") (pinfunction "2_2") (pintype "unspecified"))
      (node (ref "R49") (pin "2") (pinfunction "2_2") (pintype "input"))
      (node (ref "R6") (pin "2") (pinfunction "2_2") (pintype "input"))
      (node (ref "R7") (pin "1") (pinfunction "1_1") (pintype "input"))
      (node (ref "R74") (pin "2") (pinfunction "2_2") (pintype "input"))
      (node (ref "R8") (pin "1") (pinfunction "1_1") (pintype "input"))
      (node (ref "RESET1") (pin "1") (pinfunction "1_1") (pintype "unspecified"))
      (node (ref "RESET1") (pin "2") (pinfunction "2_2") (pintype "unspecified"))
      (node (ref "U1") (pin "10") (pinfunction "VSS_10") (pintype "unspecified"))
      (node (ref "U1") (pin "20") (pinfunction "VSSA_20") (pintype "unspecified"))
      (node (ref "U1") (pin "27") (pinfunction "VSS_27") (pintype "unspecified"))
      (node (ref "U1") (pin "74") (pinfunction "VSS_74") (pintype "unspecified"))
      (node (ref "U1") (pin "99") (pinfunction "VSS_99") (pintype "unspecified"))
      (node (ref "U10") (pin "3") (pinfunction "GND_3") (pintype "unspecified"))
      (node (ref "U11") (pin "3") (pinfunction "S_3") (pintype "unspecified"))
      (node (ref "U12") (pin "3") (pinfunction "S_3") (pintype "unspecified"))
      (node (ref "U13") (pin "8") (pinfunction "E_8") (pintype "unspecified"))
      (node (ref "U14") (pin "3") (pinfunction "S_3") (pintype "unspecified"))
      (node (ref "U16") (pin "4") (pinfunction "GND_4") (pintype "unspecified"))
      (node (ref "U19") (pin "2") (pinfunction "GND_2") (pintype "passive"))
      (node (ref "U2") (pin "3") (pinfunction "COM_3") (pintype "unspecified"))
      (node (ref "U20") (pin "4") (pinfunction "BIAS_4") (pintype "unspecified"))
      (node (ref "U20") (pin "5") (pinfunction "GND_5") (pintype "unspecified"))
      (node (ref "U20") (pin "6") (pinfunction "ZERO_EN_6") (pintype "unspecified"))
      (node (ref "U20") (pin "9") (pinfunction "INT_THRS_9") (pintype "unspecified"))
      (node (ref "U3") (pin "11") (pinfunction "VSS_11") (pintype "unspecified"))
      (node (ref "U4") (pin "11") (pinfunction "VSS_11") (pintype "unspecified"))
      (node (ref "U5") (pin "3") (pinfunction "COM_3") (pintype "unspecified"))
      (node (ref "U6") (pin "3") (pinfunction "COM_3") (pintype "unspecified"))
      (node (ref "U7") (pin "3") (pinfunction "COM_3") (pintype "unspecified"))
      (node (ref "U8") (pin "2") (pinfunction "GND_2") (pintype "unspecified"))
      (node (ref "U8") (pin "4") (pinfunction "GND_4") (pintype "unspecified"))
      (node (ref "U9") (pin "3") (pinfunction "S_3") (pintype "unspecified"))
      (node (ref "USB1") (pin "5") (pinfunction "GND_5") (pintype "unspecified"))
    )
    (net (code "41") (name "IATSensor") (class "Default")
      (node (ref "C4") (pin "2") (pinfunction "2_2") (pintype "unspecified"))
      (node (ref "R39") (pin "1") (pinfunction "1_1") (pintype "input"))
      (node (ref "R52") (pin "1") (pinfunction "1_1") (pintype "input"))
    )
    (net (code "42") (name "IDLE") (class "Default")
      (node (ref "U13") (pin "12") (pinfunction "5C_12") (pintype "unspecified"))
      (node (ref "U13") (pin "13") (pinfunction "4C_13") (pintype "unspecified"))
    )
    (net (code "43") (name "IGN1OUT") (class "Default")
      (node (ref "R72") (pin "1") (pinfunction "1_1") (pintype "input"))
      (node (ref "U6") (pin "5") (pinfunction "OUTB_5") (pintype "unspecified"))
    )
    (net (code "44") (name "IGN1_CPU") (class "Default")
      (node (ref "R25") (pin "1") (pinfunction "1_1") (pintype "input"))
      (node (ref "R30") (pin "2") (pinfunction "2_2") (pintype "input"))
      (node (ref "U1") (pin "1") (pinfunction "PE2_1") (pintype "unspecified"))
    )
    (net (code "45") (name "IGN2OUT") (class "Default")
      (node (ref "U6") (pin "7") (pinfunction "OUTA_7") (pintype "unspecified"))
    )
    (net (code "46") (name "IGN2_CPU") (class "Default")
      (node (ref "R24") (pin "1") (pinfunction "1_1") (pintype "input"))
      (node (ref "R28") (pin "1") (pinfunction "1_1") (pintype "input"))
      (node (ref "U1") (pin "2") (pinfunction "PE3_2") (pintype "unspecified"))
    )
    (net (code "47") (name "IGN3OUT") (class "Default")
      (node (ref "U7") (pin "5") (pinfunction "OUTB_5") (pintype "unspecified"))
    )
    (net (code "48") (name "IGN3_CPU") (class "Default")
      (node (ref "R27") (pin "1") (pinfunction "1_1") (pintype "input"))
      (node (ref "R32") (pin "2") (pinfunction "2_2") (pintype "input"))
      (node (ref "U1") (pin "7") (pinfunction "PC13_7") (pintype "unspecified"))
    )
    (net (code "49") (name "IGN4OUT") (class "Default")
      (node (ref "U7") (pin "7") (pinfunction "OUTA_7") (pintype "unspecified"))
    )
    (net (code "50") (name "IGN4_CPU") (class "Default")
      (node (ref "R26") (pin "1") (pinfunction "1_1") (pintype "input"))
      (node (ref "R31") (pin "1") (pinfunction "1_1") (pintype "input"))
      (node (ref "U1") (pin "38") (pinfunction "PE7_38") (pintype "unspecified"))
    )
    (net (code "51") (name "INJ-1-OUT") (class "Default")
      (node (ref "LED2") (pin "1") (pinfunction "C_1") (pintype "input"))
      (node (ref "U9") (pin "4") (pinfunction "D_4") (pintype "unspecified"))
    )
    (net (code "52") (name "INJ-2-OUT") (class "Default")
      (node (ref "U11") (pin "4") (pinfunction "D_4") (pintype "unspecified"))
    )
    (net (code "53") (name "INJ-3-OUT") (class "Default")
      (node (ref "U12") (pin "4") (pinfunction "D_4") (pintype "unspecified"))
    )
    (net (code "54") (name "INJ-4-OUT") (class "Default")
      (node (ref "U14") (pin "4") (pinfunction "D_4") (pintype "unspecified"))
    )
    (net (code "55") (name "INJ1_CPU") (class "Default")
      (node (ref "R16") (pin "1") (pinfunction "1_1") (pintype "input"))
      (node (ref "R19") (pin "1") (pinfunction "1_1") (pintype "input"))
      (node (ref "U1") (pin "54") (pinfunction "PB15_54") (pintype "unspecified"))
    )
    (net (code "56") (name "INJ2_CPU") (class "Default")
      (node (ref "R17") (pin "1") (pinfunction "1_1") (pintype "input"))
      (node (ref "R20") (pin "1") (pinfunction "1_1") (pintype "input"))
      (node (ref "U1") (pin "53") (pinfunction "PB14_53") (pintype "unspecified"))
    )
    (net (code "57") (name "INJ3_CPU") (class "Default")
      (node (ref "R18") (pin "1") (pinfunction "1_1") (pintype "input"))
      (node (ref "R23") (pin "1") (pinfunction "1_1") (pintype "input"))
      (node (ref "U1") (pin "51") (pinfunction "PB12_51") (pintype "unspecified"))
    )
    (net (code "58") (name "INJ4_CPU") (class "Default")
      (node (ref "R21") (pin "1") (pinfunction "1_1") (pintype "input"))
      (node (ref "R22") (pin "1") (pinfunction "1_1") (pintype "input"))
      (node (ref "U1") (pin "52") (pinfunction "PB13_52") (pintype "unspecified"))
    )
    (net (code "59") (name "INJ6_CPU") (class "Default")
      (node (ref "U1") (pin "41") (pinfunction "PE10_41") (pintype "unspecified"))
    )
    (net (code "60") (name "LED") (class "Default")
      (node (ref "R72") (pin "2") (pinfunction "2_2") (pintype "input"))
    )
    (net (code "61") (name "MAP") (class "Default")
      (node (ref "R53") (pin "1") (pinfunction "1_1") (pintype "input"))
      (node (ref "U10") (pin "4") (pinfunction "VOUT_4") (pintype "unspecified"))
    )
    (net (code "62") (name "NRST") (class "Default")
      (node (ref "R44") (pin "1") (pinfunction "1_1") (pintype "input"))
      (node (ref "RESET1") (pin "3") (pinfunction "3_3") (pintype "unspecified"))
      (node (ref "RESET1") (pin "4") (pinfunction "4_4") (pintype "unspecified"))
      (node (ref "U1") (pin "14") (pinfunction "NRST_14") (pintype "unspecified"))
    )
    (net (code "63") (name "Net-(C16-Pad2)") (class "Default")
      (node (ref "C16") (pin "2") (pinfunction "2_2") (pintype "unspecified"))
      (node (ref "R42") (pin "1") (pinfunction "1_1") (pintype "input"))
      (node (ref "R43") (pin "1") (pinfunction "1_1") (pintype "input"))
      (node (ref "R45") (pin "2") (pinfunction "2_2") (pintype "input"))
    )
    (net (code "64") (name "Net-(LED1-C)") (class "Default")
      (node (ref "LED1") (pin "2") (pinfunction "C_2") (pintype "input"))
      (node (ref "R33") (pin "1") (pinfunction "1_1") (pintype "input"))
    )
    (net (code "65") (name "Net-(LED2-A)") (class "Default")
      (node (ref "LED2") (pin "2") (pinfunction "A_2") (pintype "input"))
      (node (ref "R62") (pin "2") (pinfunction "2_2") (pintype "input"))
    )
    (net (code "66") (name "Net-(U1-VCAP_1)") (class "Default")
      (node (ref "C76") (pin "1") (pinfunction "1_1") (pintype "unspecified"))
      (node (ref "U1") (pin "49") (pinfunction "VCAP_1_49") (pintype "unspecified"))
    )
    (net (code "67") (name "Net-(U1-VCAP_2)") (class "Default")
      (node (ref "C75") (pin "2") (pinfunction "2_2") (pintype "unspecified"))
      (node (ref "U1") (pin "73") (pinfunction "VCAP_2_73") (pintype "unspecified"))
    )
    (net (code "68") (name "Net-(U2-INA)") (class "Default")
      (node (ref "R19") (pin "2") (pinfunction "2_2") (pintype "input"))
      (node (ref "U2") (pin "2") (pinfunction "INA_2") (pintype "unspecified"))
    )
    (net (code "69") (name "Net-(U2-INB)") (class "Default")
      (node (ref "R20") (pin "2") (pinfunction "2_2") (pintype "input"))
      (node (ref "U2") (pin "4") (pinfunction "INB_4") (pintype "unspecified"))
    )
    (net (code "70") (name "Net-(U3-VINA-)") (class "Default")
      (node (ref "R9") (pin "2") (pinfunction "2_2") (pintype "unspecified"))
      (node (ref "U3") (pin "1") (pinfunction "VOUTA_1") (pintype "unspecified"))
      (node (ref "U3") (pin "2") (pinfunction "VINA-_2") (pintype "unspecified"))
    )
    (net (code "71") (name "Net-(U3-VINB-)") (class "Default")
      (node (ref "R13") (pin "2") (pinfunction "2_2") (pintype "unspecified"))
      (node (ref "U3") (pin "6") (pinfunction "VINB-_6") (pintype "unspecified"))
      (node (ref "U3") (pin "7") (pinfunction "VOUTB_7") (pintype "unspecified"))
    )
    (net (code "72") (name "Net-(U3-VINC-)") (class "Default")
      (node (ref "R11") (pin "1") (pinfunction "1_1") (pintype "unspecified"))
      (node (ref "U3") (pin "8") (pinfunction "VOUTC_8") (pintype "unspecified"))
      (node (ref "U3") (pin "9") (pinfunction "VINC-_9") (pintype "unspecified"))
    )
    (net (code "73") (name "Net-(U3-VIND-)") (class "Default")
      (node (ref "R10") (pin "1") (pinfunction "1_1") (pintype "unspecified"))
      (node (ref "U3") (pin "13") (pinfunction "VIND-_13") (pintype "unspecified"))
      (node (ref "U3") (pin "14") (pinfunction "VOUTD_14") (pintype "unspecified"))
    )
    (net (code "74") (name "Net-(U4-VINA-)") (class "Default")
      (node (ref "R12") (pin "2") (pinfunction "2_2") (pintype "unspecified"))
      (node (ref "U4") (pin "1") (pinfunction "VOUTA_1") (pintype "unspecified"))
      (node (ref "U4") (pin "2") (pinfunction "VINA-_2") (pintype "unspecified"))
    )
    (net (code "75") (name "Net-(U4-VIND-)") (class "Default")
      (node (ref "R14") (pin "2") (pinfunction "2_2") (pintype "unspecified"))
      (node (ref "U4") (pin "13") (pinfunction "VIND-_13") (pintype "unspecified"))
      (node (ref "U4") (pin "14") (pinfunction "VOUTD_14") (pintype "unspecified"))
    )
    (net (code "76") (name "Net-(U5-INA)") (class "Default")
      (node (ref "R18") (pin "2") (pinfunction "2_2") (pintype "input"))
      (node (ref "U5") (pin "2") (pinfunction "INA_2") (pintype "unspecified"))
    )
    (net (code "77") (name "Net-(U5-INB)") (class "Default")
      (node (ref "R21") (pin "2") (pinfunction "2_2") (pintype "input"))
      (node (ref "U5") (pin "4") (pinfunction "INB_4") (pintype "unspecified"))
    )
    (net (code "78") (name "Net-(U6-INA)") (class "Default")
      (node (ref "R24") (pin "2") (pinfunction "2_2") (pintype "input"))
      (node (ref "U6") (pin "2") (pinfunction "INA_2") (pintype "unspecified"))
    )
    (net (code "79") (name "Net-(U6-INB)") (class "Default")
      (node (ref "R25") (pin "2") (pinfunction "2_2") (pintype "input"))
      (node (ref "U6") (pin "4") (pinfunction "INB_4") (pintype "unspecified"))
    )
    (net (code "80") (name "Net-(U7-INA)") (class "Default")
      (node (ref "R26") (pin "2") (pinfunction "2_2") (pintype "input"))
      (node (ref "U7") (pin "2") (pinfunction "INA_2") (pintype "unspecified"))
    )
    (net (code "81") (name "Net-(U7-INB)") (class "Default")
      (node (ref "R27") (pin "2") (pinfunction "2_2") (pintype "input"))
      (node (ref "U7") (pin "4") (pinfunction "INB_4") (pintype "unspecified"))
    )
    (net (code "82") (name "Net-(U9-G)") (class "Default")
      (node (ref "R68") (pin "2") (pinfunction "2_2") (pintype "input"))
      (node (ref "U9") (pin "1") (pinfunction "G_1") (pintype "unspecified"))
    )
    (net (code "83") (name "Net-(U11-G)") (class "Default")
      (node (ref "R70") (pin "2") (pinfunction "2_2") (pintype "input"))
      (node (ref "U11") (pin "1") (pinfunction "G_1") (pintype "unspecified"))
    )
    (net (code "84") (name "Net-(U12-G)") (class "Default")
      (node (ref "R69") (pin "2") (pinfunction "2_2") (pintype "input"))
      (node (ref "U12") (pin "1") (pinfunction "G_1") (pintype "unspecified"))
    )
    (net (code "85") (name "Net-(U14-G)") (class "Default")
      (node (ref "R67") (pin "2") (pinfunction "2_2") (pintype "input"))
      (node (ref "U14") (pin "1") (pinfunction "G_1") (pintype "unspecified"))
    )
    (net (code "86") (name "Net-(U16-CLK)") (class "Default")
      (node (ref "R41") (pin "1") (pinfunction "1_1") (pintype "input"))
      (node (ref "U16") (pin "6") (pinfunction "CLK_6") (pintype "unspecified"))
    )
    (net (code "87") (name "Net-(U20-IN+)") (class "Default")
      (node (ref "C20") (pin "2") (pinfunction "2_2") (pintype "unspecified"))
      (node (ref "R76") (pin "2") (pinfunction "2_2") (pintype "input"))
      (node (ref "U20") (pin "1") (pinfunction "IN+_1") (pintype "unspecified"))
    )
    (net (code "88") (name "Net-(U20-IN-)") (class "Default")
      (node (ref "C20") (pin "1") (pinfunction "1_1") (pintype "unspecified"))
      (node (ref "R75") (pin "2") (pinfunction "2_2") (pintype "input"))
      (node (ref "U20") (pin "2") (pinfunction "IN-_2") (pintype "unspecified"))
    )
    (net (code "89") (name "OSC32_IN") (class "Default")
      (node (ref "C26") (pin "2") (pinfunction "2_2") (pintype "input"))
      (node (ref "U1") (pin "8") (pinfunction "PC14_8") (pintype "unspecified"))
      (node (ref "X2") (pin "2") (pinfunction "2_2") (pintype "unspecified"))
    )
    (net (code "90") (name "OSC32_OUT") (class "Default")
      (node (ref "C25") (pin "2") (pinfunction "2_2") (pintype "input"))
      (node (ref "U1") (pin "9") (pinfunction "PC15_9") (pintype "unspecified"))
      (node (ref "X2") (pin "1") (pinfunction "1_1") (pintype "unspecified"))
    )
    (net (code "91") (name "OSC_IN") (class "Default")
      (node (ref "C31") (pin "2") (pinfunction "2_2") (pintype "input"))
      (node (ref "R29") (pin "1") (pinfunction "1_1") (pintype "input"))
      (node (ref "U1") (pin "12") (pinfunction "PH0_12") (pintype "unspecified"))
      (node (ref "X1") (pin "2") (pinfunction "OSC2_2") (pintype "input"))
    )
    (net (code "92") (name "OSC_OUT") (class "Default")
      (node (ref "C29") (pin "2") (pinfunction "2_2") (pintype "input"))
      (node (ref "R29") (pin "2") (pinfunction "2_2") (pintype "input"))
      (node (ref "U1") (pin "13") (pinfunction "PH1_13") (pintype "unspecified"))
      (node (ref "X1") (pin "1") (pinfunction "OSC1_1") (pintype "input"))
    )
    (net (code "93") (name "PA0") (class "Default")
      (node (ref "R8") (pin "2") (pinfunction "2_2") (pintype "input"))
      (node (ref "R9") (pin "1") (pinfunction "1_1") (pintype "unspecified"))
      (node (ref "U1") (pin "23") (pinfunction "PA0_23") (pintype "unspecified"))
    )
    (net (code "94") (name "PA1") (class "Default")
      (node (ref "R13") (pin "1") (pinfunction "1_1") (pintype "unspecified"))
      (node (ref "R7") (pin "2") (pinfunction "2_2") (pintype "input"))
      (node (ref "U1") (pin "24") (pinfunction "PA1_24") (pintype "unspecified"))
    )
    (net (code "95") (name "PA2") (class "Default")
      (node (ref "R10") (pin "2") (pinfunction "2_2") (pintype "unspecified"))
      (node (ref "R6") (pin "1") (pinfunction "1_1") (pintype "input"))
      (node (ref "U1") (pin "25") (pinfunction "PA2_25") (pintype "unspecified"))
    )
    (net (code "96") (name "PA3") (class "Default")
      (node (ref "R11") (pin "2") (pinfunction "2_2") (pintype "unspecified"))
      (node (ref "R4") (pin "1") (pinfunction "1_1") (pintype "input"))
      (node (ref "U1") (pin "26") (pinfunction "PA3_26") (pintype "unspecified"))
    )
    (net (code "97") (name "PA4") (class "Default")
      (node (ref "R12") (pin "1") (pinfunction "1_1") (pintype "unspecified"))
      (node (ref "R2") (pin "2") (pinfunction "2_2") (pintype "input"))
      (node (ref "U1") (pin "29") (pinfunction "PA4_29") (pintype "unspecified"))
    )
    (net (code "98") (name "PA5") (class "Default")
      (node (ref "U1") (pin "30") (pinfunction "PA5_30") (pintype "unspecified"))
    )
    (net (code "99") (name "PA6") (class "Default")
      (node (ref "U1") (pin "31") (pinfunction "PA6_31") (pintype "unspecified"))
    )
    (net (code "100") (name "PA7") (class "Default")
      (node (ref "U1") (pin "32") (pinfunction "PA7_32") (pintype "unspecified"))
    )
    (net (code "101") (name "PA8") (class "Default")
      (node (ref "U1") (pin "67") (pinfunction "PA8_67") (pintype "unspecified"))
    )
    (net (code "102") (name "PB0") (class "Default")
      (node (ref "R14") (pin "1") (pinfunction "1_1") (pintype "unspecified"))
      (node (ref "R15") (pin "2") (pinfunction "2_2") (pintype "input"))
      (node (ref "U1") (pin "35") (pinfunction "PB0_35") (pintype "unspecified"))
    )
    (net (code "103") (name "PB1") (class "Default")
      (node (ref "U1") (pin "36") (pinfunction "PB1_36") (pintype "unspecified"))
    )
    (net (code "104") (name "PB6") (class "Default")
      (node (ref "U1") (pin "92") (pinfunction "PB6_92") (pintype "unspecified"))
    )
    (net (code "105") (name "PB7") (class "Default")
      (node (ref "U1") (pin "93") (pinfunction "PB7_93") (pintype "unspecified"))
    )
    (net (code "106") (name "PB8") (class "Default")
      (node (ref "R1") (pin "1") (pinfunction "1_1") (pintype "input"))
      (node (ref "U1") (pin "95") (pinfunction "PB8_95") (pintype "unspecified"))
    )
    (net (code "107") (name "PB9") (class "Default")
      (node (ref "U1") (pin "96") (pinfunction "PB9_96") (pintype "unspecified"))
    )
    (net (code "108") (name "PB10") (class "Default")
      (node (ref "U1") (pin "47") (pinfunction "PB10_47") (pintype "unspecified"))
    )
    (net (code "109") (name "PB11") (class "Default")
      (node (ref "U1") (pin "48") (pinfunction "PB11_48") (pintype "unspecified"))
    )
    (net (code "110") (name "PC0") (class "Default")
      (node (ref "U1") (pin "15") (pinfunction "PC0_15") (pintype "unspecified"))
    )
    (net (code "111") (name "PC1") (class "Default")
      (node (ref "U1") (pin "16") (pinfunction "PC1_16") (pintype "unspecified"))
    )
    (net (code "112") (name "PC2") (class "Default")
      (node (ref "U1") (pin "17") (pinfunction "PC2_17") (pintype "unspecified"))
    )
    (net (code "113") (name "PC3") (class "Default")
      (node (ref "U1") (pin "18") (pinfunction "PC3_18") (pintype "unspecified"))
    )
    (net (code "114") (name "PC4") (class "Default")
      (node (ref "U1") (pin "33") (pinfunction "PC4_33") (pintype "unspecified"))
    )
    (net (code "115") (name "PC5") (class "Default")
      (node (ref "U1") (pin "34") (pinfunction "PC5_34") (pintype "unspecified"))
    )
    (net (code "116") (name "PC10") (class "Default")
      (node (ref "U1") (pin "78") (pinfunction "PC10_78") (pintype "unspecified"))
    )
    (net (code "117") (name "PC11") (class "Default")
      (node (ref "U1") (pin "79") (pinfunction "PC11_79") (pintype "unspecified"))
    )
    (net (code "118") (name "PC12") (class "Default")
      (node (ref "U1") (pin "80") (pinfunction "PC12_80") (pintype "unspecified"))
    )
    (net (code "119") (name "PD2") (class "Default")
      (node (ref "U1") (pin "83") (pinfunction "PD2_83") (pintype "unspecified"))
    )
    (net (code "120") (name "PD5") (class "Default")
      (node (ref "U1") (pin "86") (pinfunction "PD5_86") (pintype "unspecified"))
    )
    (net (code "121") (name "PD6") (class "Default")
      (node (ref "U1") (pin "87") (pinfunction "PD6_87") (pintype "unspecified"))
    )
    (net (code "122") (name "PD7") (class "Default")
      (node (ref "U1") (pin "88") (pinfunction "PD7_88") (pintype "unspecified"))
    )
    (net (code "123") (name "PD8") (class "Default")
      (node (ref "U1") (pin "55") (pinfunction "PD8_55") (pintype "unspecified"))
    )
    (net (code "124") (name "PD10") (class "Default")
      (node (ref "U1") (pin "57") (pinfunction "PD10_57") (pintype "unspecified"))
    )
    (net (code "125") (name "PD11") (class "Default")
      (node (ref "U1") (pin "58") (pinfunction "PD11_58") (pintype "unspecified"))
    )
    (net (code "126") (name "PD12") (class "Default")
      (node (ref "U1") (pin "59") (pinfunction "PD12_59") (pintype "unspecified"))
    )
    (net (code "127") (name "PD13") (class "Default")
      (node (ref "U1") (pin "60") (pinfunction "PD13_60") (pintype "unspecified"))
    )
    (net (code "128") (name "PE0") (class "Default")
      (node (ref "U1") (pin "97") (pinfunction "PE0_97") (pintype "unspecified"))
    )
    (net (code "129") (name "PE1") (class "Default")
      (node (ref "U1") (pin "98") (pinfunction "PE1_98") (pintype "unspecified"))
    )
    (net (code "130") (name "PE5") (class "Default")
      (node (ref "U1") (pin "4") (pinfunction "PE5_4") (pintype "unspecified"))
    )
    (net (code "131") (name "PE6") (class "Default")
      (node (ref "U1") (pin "5") (pinfunction "PE6_5") (pintype "unspecified"))
    )
    (net (code "132") (name "PE12") (class "Default")
      (node (ref "U1") (pin "43") (pinfunction "PE12_43") (pintype "unspecified"))
    )
    (net (code "133") (name "PE13") (class "Default")
      (node (ref "U1") (pin "44") (pinfunction "PE13_44") (pintype "unspecified"))
    )
    (net (code "134") (name "PE14") (class "Default")
      (node (ref "U1") (pin "45") (pinfunction "PE14_45") (pintype "unspecified"))
    )
    (net (code "135") (name "PE15") (class "Default")
      (node (ref "U1") (pin "46") (pinfunction "PE15_46") (pintype "unspecified"))
    )
    (net (code "136") (name "RX_CPU") (class "Default")
      (node (ref "U1") (pin "69") (pinfunction "PA10_69") (pintype "unspecified"))
    )
    (net (code "137") (name "SPARE") (class "Default")
      (node (ref "U13") (pin "10") (pinfunction "7C_10") (pintype "unspecified"))
      (node (ref "U13") (pin "11") (pinfunction "6C_11") (pintype "unspecified"))
    )
    (net (code "138") (name "SPI1 CLK") (class "Default")
      (node (ref "R41") (pin "2") (pinfunction "2_2") (pintype "input"))
      (node (ref "U1") (pin "89") (pinfunction "PB3_89") (pintype "unspecified"))
    )
    (net (code "139") (name "SPI1 MISO") (class "Default")
      (node (ref "U1") (pin "90") (pinfunction "PB4_90") (pintype "unspecified"))
      (node (ref "U16") (pin "2") (pinfunction "DO/IO1_2") (pintype "unspecified"))
    )
    (net (code "140") (name "SPI1 MOSI") (class "Default")
      (node (ref "U1") (pin "91") (pinfunction "PB5_91") (pintype "unspecified"))
      (node (ref "U16") (pin "5") (pinfunction "DI/IO0_5") (pintype "unspecified"))
    )
    (net (code "141") (name "SPR") (class "Default")
      (node (ref "U13") (pin "6") (pinfunction "6B_6") (pintype "unspecified"))
      (node (ref "U13") (pin "7") (pinfunction "7B_7") (pintype "unspecified"))
    )
    (net (code "142") (name "SWCLK") (class "Default")
      (node (ref "H5") (pin "3") (pinfunction "3_3") (pintype "unspecified"))
      (node (ref "R49") (pin "1") (pinfunction "1_1") (pintype "input"))
      (node (ref "U1") (pin "76") (pinfunction "PA14_76") (pintype "unspecified"))
    )
    (net (code "143") (name "SWDIO") (class "Default")
      (node (ref "H5") (pin "2") (pinfunction "2_2") (pintype "unspecified"))
      (node (ref "R37") (pin "1") (pinfunction "1_1") (pintype "input"))
      (node (ref "U1") (pin "72") (pinfunction "PA13_72") (pintype "unspecified"))
    )
    (net (code "144") (name "TACH-CPU-D19") (class "Default")
      (node (ref "C18") (pin "2") (pinfunction "2_2") (pintype "unspecified"))
      (node (ref "R34") (pin "2") (pinfunction "2_2") (pintype "input"))
    )
    (net (code "145") (name "TACH1-CPU-D19") (class "Default")
      (node (ref "R73") (pin "2") (pinfunction "2_2") (pintype "input"))
      (node (ref "U20") (pin "7") (pinfunction "COUT_7") (pintype "unspecified"))
    )
    (net (code "146") (name "TACHO") (class "Default")
      (node (ref "R71") (pin "1") (pinfunction "1_1") (pintype "input"))
      (node (ref "U13") (pin "14") (pinfunction "3C_14") (pintype "unspecified"))
    )
    (net (code "147") (name "TPSSensor") (class "Default")
      (node (ref "C10") (pin "2") (pinfunction "2_2") (pintype "unspecified"))
      (node (ref "R50") (pin "1") (pinfunction "1_1") (pintype "input"))
    )
    (net (code "148") (name "TX_CPU") (class "Default")
      (node (ref "U1") (pin "68") (pinfunction "PA9_68") (pintype "unspecified"))
    )
    (net (code "149") (name "USB_OTG+") (class "Default")
      (node (ref "U1") (pin "71") (pinfunction "PA12_71") (pintype "unspecified"))
      (node (ref "USB1") (pin "3") (pinfunction "D+_3") (pintype "unspecified"))
    )
    (net (code "150") (name "USB_OTG-") (class "Default")
      (node (ref "U1") (pin "70") (pinfunction "PA11_70") (pintype "unspecified"))
      (node (ref "USB1") (pin "2") (pinfunction "D-_2") (pintype "unspecified"))
    )
    (net (code "151") (name "VBAT") (class "Default")
      (node (ref "U1") (pin "6") (pinfunction "VBAT_6") (pintype "unspecified"))
    )
    (net (code "152") (name "VBUS") (class "Default")
      (node (ref "D1") (pin "2") (pinfunction "A_2") (pintype "unspecified"))
      (node (ref "USB1") (pin "1") (pinfunction "VBUS_1") (pintype "unspecified"))
    )
    (net (code "153") (name "VDD") (class "Default")
      (node (ref "U2") (pin "6") (pinfunction "VCC_6") (pintype "unspecified"))
      (node (ref "U5") (pin "6") (pinfunction "VCC_6") (pintype "unspecified"))
    )
    (net (code "154") (name "VDDI") (class "Default")
      (node (ref "U6") (pin "6") (pinfunction "VCC_6") (pintype "unspecified"))
      (node (ref "U7") (pin "6") (pinfunction "VCC_6") (pintype "unspecified"))
    )
    (net (code "155") (name "VIN") (class "Default")
      (node (ref "D3") (pin "1") (pinfunction "A_1") (pintype "unspecified"))
      (node (ref "R3") (pin "1") (pinfunction "1_1") (pintype "unspecified"))
    )
    (net (code "156") (name "VREF+") (class "Default")
      (node (ref "R5") (pin "2") (pinfunction "2_2") (pintype "input"))
      (node (ref "R74") (pin "1") (pinfunction "1_1") (pintype "input"))
      (node (ref "U1") (pin "21") (pinfunction "VREF+_21") (pintype "unspecified"))
    )
    (net (code "157") (name "unconnected-(R75-Pad1)") (class "Default")
      (node (ref "R75") (pin "1") (pinfunction "1_1") (pintype "input"))
    )
    (net (code "158") (name "unconnected-(R76-Pad1)") (class "Default")
      (node (ref "R76") (pin "1") (pinfunction "1_1") (pintype "input"))
    )
    (net (code "159") (name "unconnected-(U2-NC-Pad1)") (class "Default")
      (node (ref "U2") (pin "1") (pinfunction "NC_1") (pintype "unspecified"))
    )
    (net (code "160") (name "unconnected-(U2-NC-Pad8)") (class "Default")
      (node (ref "U2") (pin "8") (pinfunction "NC_8") (pintype "unspecified"))
    )
    (net (code "161") (name "unconnected-(U4-VINB+-Pad5)") (class "Default")
      (node (ref "U4") (pin "5") (pinfunction "VINB+_5") (pintype "unspecified"))
    )
    (net (code "162") (name "unconnected-(U4-VINB--Pad6)") (class "Default")
      (node (ref "U4") (pin "6") (pinfunction "VINB-_6") (pintype "unspecified"))
    )
    (net (code "163") (name "unconnected-(U4-VINC+-Pad10)") (class "Default")
      (node (ref "U4") (pin "10") (pinfunction "VINC+_10") (pintype "unspecified"))
    )
    (net (code "164") (name "unconnected-(U4-VINC--Pad9)") (class "Default")
      (node (ref "U4") (pin "9") (pinfunction "VINC-_9") (pintype "unspecified"))
    )
    (net (code "165") (name "unconnected-(U4-VOUTB-Pad7)") (class "Default")
      (node (ref "U4") (pin "7") (pinfunction "VOUTB_7") (pintype "unspecified"))
    )
    (net (code "166") (name "unconnected-(U4-VOUTC-Pad8)") (class "Default")
      (node (ref "U4") (pin "8") (pinfunction "VOUTC_8") (pintype "unspecified"))
    )
    (net (code "167") (name "unconnected-(U5-NC-Pad1)") (class "Default")
      (node (ref "U5") (pin "1") (pinfunction "NC_1") (pintype "unspecified"))
    )
    (net (code "168") (name "unconnected-(U5-NC-Pad8)") (class "Default")
      (node (ref "U5") (pin "8") (pinfunction "NC_8") (pintype "unspecified"))
    )
    (net (code "169") (name "unconnected-(U6-NC-Pad1)") (class "Default")
      (node (ref "U6") (pin "1") (pinfunction "NC_1") (pintype "unspecified"))
    )
    (net (code "170") (name "unconnected-(U6-NC-Pad8)") (class "Default")
      (node (ref "U6") (pin "8") (pinfunction "NC_8") (pintype "unspecified"))
    )
    (net (code "171") (name "unconnected-(U7-NC-Pad1)") (class "Default")
      (node (ref "U7") (pin "1") (pinfunction "NC_1") (pintype "unspecified"))
    )
    (net (code "172") (name "unconnected-(U7-NC-Pad8)") (class "Default")
      (node (ref "U7") (pin "8") (pinfunction "NC_8") (pintype "unspecified"))
    )
    (net (code "173") (name "unconnected-(U10-DNC-Pad1)") (class "Default")
      (node (ref "U10") (pin "1") (pinfunction "DNC_1") (pintype "unspecified"))
    )
    (net (code "174") (name "unconnected-(U10-DNC-Pad5)") (class "Default")
      (node (ref "U10") (pin "5") (pinfunction "DNC_5") (pintype "unspecified"))
    )
    (net (code "175") (name "unconnected-(U10-DNC-Pad6)") (class "Default")
      (node (ref "U10") (pin "6") (pinfunction "DNC_6") (pintype "unspecified"))
    )
    (net (code "176") (name "unconnected-(U10-DNC-Pad7)") (class "Default")
      (node (ref "U10") (pin "7") (pinfunction "DNC_7") (pintype "unspecified"))
    )
    (net (code "177") (name "unconnected-(U10-DNC-Pad8)") (class "Default")
      (node (ref "U10") (pin "8") (pinfunction "DNC_8") (pintype "unspecified"))
    )
    (net (code "178") (name "unconnected-(U20-EXT-Pad8)") (class "Default")
      (node (ref "U20") (pin "8") (pinfunction "EXT_8") (pintype "unspecified+no_connect"))
    )
    (net (code "179") (name "unconnected-(U20-NC-Pad3)") (class "Default")
      (node (ref "U20") (pin "3") (pinfunction "NC_3") (pintype "unspecified+no_connect"))
    )
    (net (code "180") (name "unconnected-(USB1-EP-Pad6)") (class "Default")
      (node (ref "USB1") (pin "6") (pinfunction "EP_6") (pintype "unspecified"))
    )
    (net (code "181") (name "unconnected-(USB1-EP-Pad7)") (class "Default")
      (node (ref "USB1") (pin "7") (pinfunction "EP_7") (pintype "unspecified"))
    )
    (net (code "182") (name "unconnected-(USB1-EP-Pad8)") (class "Default")
      (node (ref "USB1") (pin "8") (pinfunction "EP_8") (pintype "unspecified"))
    )
    (net (code "183") (name "unconnected-(USB1-EP-Pad9)") (class "Default")
      (node (ref "USB1") (pin "9") (pinfunction "EP_9") (pintype "unspecified"))
    )
    (net (code "184") (name "unconnected-(USB1-ID-Pad4)") (class "Default")
      (node (ref "USB1") (pin "4") (pinfunction "ID_4") (pintype "unspecified"))
    )
  )
)
